# FPGA_PPU.net
KiCad netlist of a schematic drawn in EAGLE
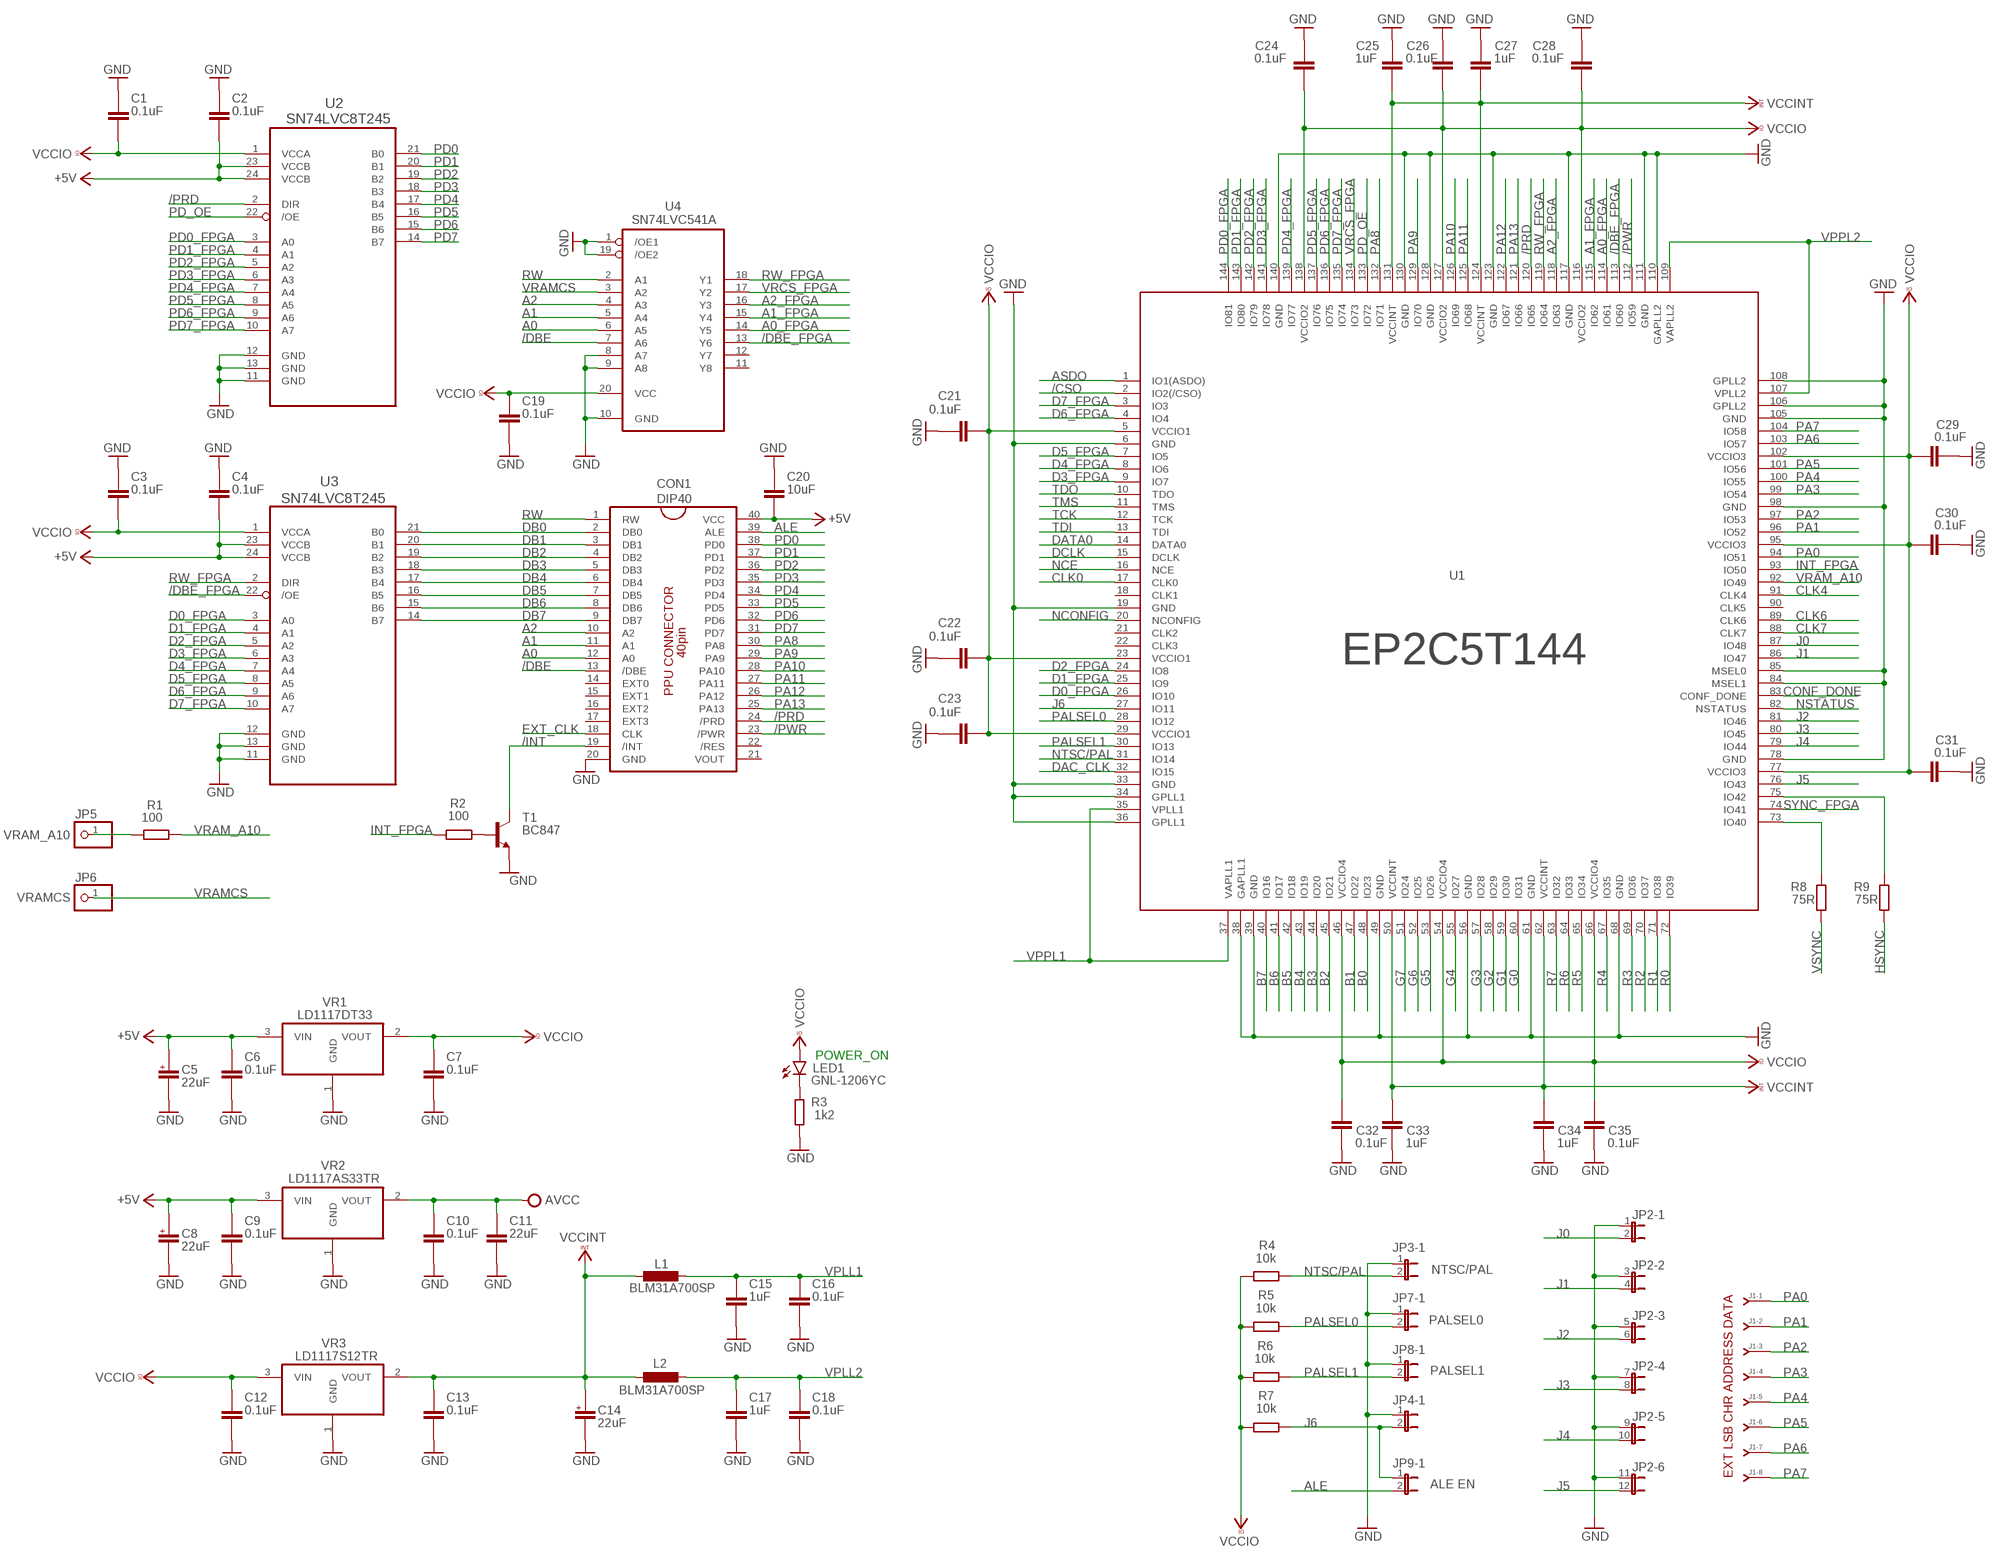
[diagram p0: schematic, sheet 1, part 1 of 2]
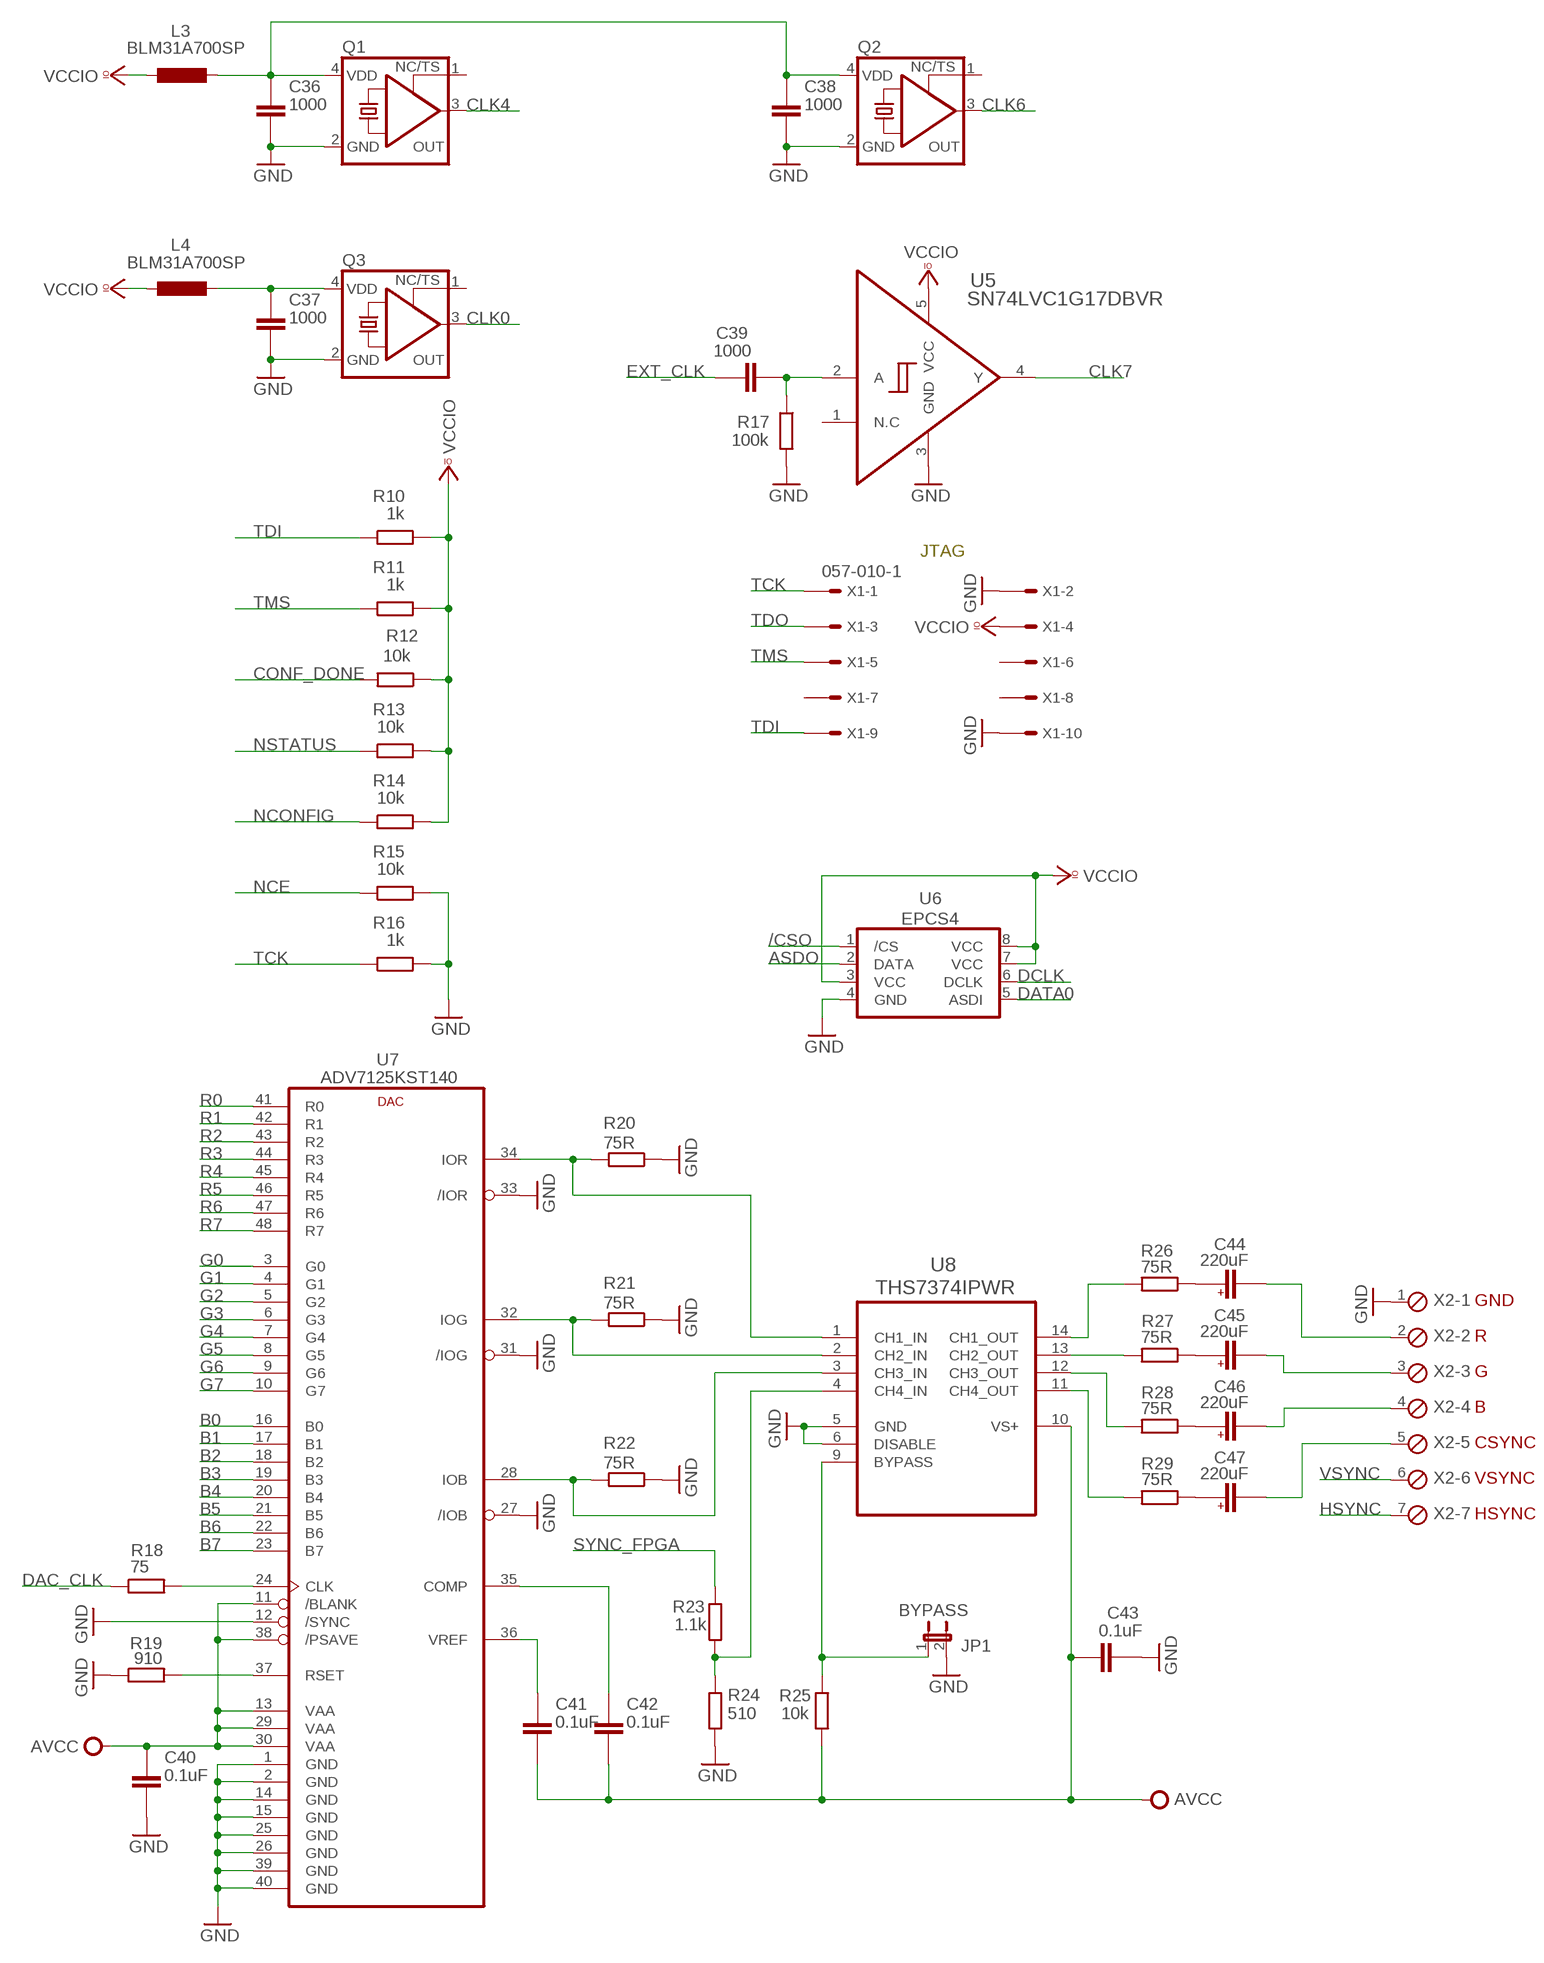
[diagram p1: schematic, sheet 1, part 2 of 2]

(export (version "E")
  (design (tool "Eeschema 10.0.6"))
  (components
    (comp (ref "C1")
      (value "0.1uF")
      (footprint "eagle-import:C0805")
      (libsource (lib "eagle-import") (part "C-EUC0805"))
    )
    (comp (ref "C2")
      (value "0.1uF")
      (footprint "eagle-import:C0805")
      (libsource (lib "eagle-import") (part "C-EUC0805"))
    )
    (comp (ref "C3")
      (value "0.1uF")
      (footprint "eagle-import:C0805")
      (libsource (lib "eagle-import") (part "C-EUC0805"))
    )
    (comp (ref "C4")
      (value "0.1uF")
      (footprint "eagle-import:C0805")
      (libsource (lib "eagle-import") (part "C-EUC0805"))
    )
    (comp (ref "C5")
      (value "22uF")
      (footprint "eagle-import:153CLV-0505")
      (libsource (lib "eagle-import") (part "CPOL-EU153CLV-0505"))
    )
    (comp (ref "C6")
      (value "0.1uF")
      (footprint "eagle-import:C0805")
      (libsource (lib "eagle-import") (part "C-EUC0805"))
    )
    (comp (ref "C7")
      (value "0.1uF")
      (footprint "eagle-import:C0805")
      (libsource (lib "eagle-import") (part "C-EUC0805"))
    )
    (comp (ref "C8")
      (value "22uF")
      (footprint "eagle-import:153CLV-0505")
      (libsource (lib "eagle-import") (part "CPOL-EU153CLV-0505"))
    )
    (comp (ref "C9")
      (value "0.1uF")
      (footprint "eagle-import:C0805")
      (libsource (lib "eagle-import") (part "C-EUC0805"))
    )
    (comp (ref "C10")
      (value "0.1uF")
      (footprint "eagle-import:C0805")
      (libsource (lib "eagle-import") (part "C-EUC0805"))
    )
    (comp (ref "C11")
      (value "22uF")
      (footprint "eagle-import:C0805")
      (libsource (lib "eagle-import") (part "C-EUC0805"))
    )
    (comp (ref "C12")
      (value "0.1uF")
      (footprint "eagle-import:C0805")
      (libsource (lib "eagle-import") (part "C-EUC0805"))
    )
    (comp (ref "C13")
      (value "0.1uF")
      (footprint "eagle-import:C0805")
      (libsource (lib "eagle-import") (part "C-EUC0805"))
    )
    (comp (ref "C14")
      (value "22uF")
      (footprint "eagle-import:153CLV-0505")
      (libsource (lib "eagle-import") (part "CPOL-EU153CLV-0505"))
    )
    (comp (ref "C15")
      (value "1uF")
      (footprint "eagle-import:C0805")
      (libsource (lib "eagle-import") (part "C-EUC0805"))
    )
    (comp (ref "C16")
      (value "0.1uF")
      (footprint "eagle-import:C0805")
      (libsource (lib "eagle-import") (part "C-EUC0805"))
    )
    (comp (ref "C17")
      (value "1uF")
      (footprint "eagle-import:C0805")
      (libsource (lib "eagle-import") (part "C-EUC0805"))
    )
    (comp (ref "C18")
      (value "0.1uF")
      (footprint "eagle-import:C0805")
      (libsource (lib "eagle-import") (part "C-EUC0805"))
    )
    (comp (ref "C19")
      (value "0.1uF")
      (footprint "eagle-import:C0805")
      (libsource (lib "eagle-import") (part "C-EUC0805"))
    )
    (comp (ref "C20")
      (value "10uF")
      (footprint "eagle-import:C0805")
      (libsource (lib "eagle-import") (part "C-EUC0805"))
    )
    (comp (ref "C21")
      (value "0.1uF")
      (footprint "eagle-import:C0805")
      (libsource (lib "eagle-import") (part "C-EUC0805"))
    )
    (comp (ref "C22")
      (value "0.1uF")
      (footprint "eagle-import:C0805")
      (libsource (lib "eagle-import") (part "C-EUC0805"))
    )
    (comp (ref "C23")
      (value "0.1uF")
      (footprint "eagle-import:C0805")
      (libsource (lib "eagle-import") (part "C-EUC0805"))
    )
    (comp (ref "C24")
      (value "0.1uF")
      (footprint "eagle-import:C0805")
      (libsource (lib "eagle-import") (part "C-EUC0805"))
    )
    (comp (ref "C25")
      (value "1uF")
      (footprint "eagle-import:C0805")
      (libsource (lib "eagle-import") (part "C-EUC0805"))
    )
    (comp (ref "C26")
      (value "0.1uF")
      (footprint "eagle-import:C0805")
      (libsource (lib "eagle-import") (part "C-EUC0805"))
    )
    (comp (ref "C27")
      (value "1uF")
      (footprint "eagle-import:C0805")
      (libsource (lib "eagle-import") (part "C-EUC0805"))
    )
    (comp (ref "C28")
      (value "0.1uF")
      (footprint "eagle-import:C0805")
      (libsource (lib "eagle-import") (part "C-EUC0805"))
    )
    (comp (ref "C29")
      (value "0.1uF")
      (footprint "eagle-import:C0805")
      (libsource (lib "eagle-import") (part "C-EUC0805"))
    )
    (comp (ref "C30")
      (value "0.1uF")
      (footprint "eagle-import:C0805")
      (libsource (lib "eagle-import") (part "C-EUC0805"))
    )
    (comp (ref "C31")
      (value "0.1uF")
      (footprint "eagle-import:C0805")
      (libsource (lib "eagle-import") (part "C-EUC0805"))
    )
    (comp (ref "C32")
      (value "0.1uF")
      (footprint "eagle-import:C0805")
      (libsource (lib "eagle-import") (part "C-EUC0805"))
    )
    (comp (ref "C33")
      (value "1uF")
      (footprint "eagle-import:C0805")
      (libsource (lib "eagle-import") (part "C-EUC0805"))
    )
    (comp (ref "C34")
      (value "1uF")
      (footprint "eagle-import:C0805")
      (libsource (lib "eagle-import") (part "C-EUC0805"))
    )
    (comp (ref "C35")
      (value "0.1uF")
      (footprint "eagle-import:C0805")
      (libsource (lib "eagle-import") (part "C-EUC0805"))
    )
    (comp (ref "C36")
      (value "1000")
      (footprint "eagle-import:C0805")
      (libsource (lib "eagle-import") (part "C-EUC0805"))
    )
    (comp (ref "C37")
      (value "1000")
      (footprint "eagle-import:C0805")
      (libsource (lib "eagle-import") (part "C-EUC0805"))
    )
    (comp (ref "C38")
      (value "1000")
      (footprint "eagle-import:C0805")
      (libsource (lib "eagle-import") (part "C-EUC0805"))
    )
    (comp (ref "C39")
      (value "1000")
      (footprint "eagle-import:C0805")
      (libsource (lib "eagle-import") (part "C-EUC0805"))
    )
    (comp (ref "C40")
      (value "0.1uF")
      (footprint "eagle-import:C0805")
      (libsource (lib "eagle-import") (part "C-EUC0805"))
    )
    (comp (ref "C41")
      (value "0.1uF")
      (footprint "eagle-import:C0805")
      (libsource (lib "eagle-import") (part "C-EUC0805"))
    )
    (comp (ref "C42")
      (value "0.1uF")
      (footprint "eagle-import:C0805")
      (libsource (lib "eagle-import") (part "C-EUC0805"))
    )
    (comp (ref "C43")
      (value "0.1uF")
      (footprint "eagle-import:C0805")
      (libsource (lib "eagle-import") (part "C-EUC0805"))
    )
    (comp (ref "C44")
      (value "220uF")
      (footprint "eagle-import:153CLV-0505")
      (libsource (lib "eagle-import") (part "CPOL-EU153CLV-0505"))
    )
    (comp (ref "C45")
      (value "220uF")
      (footprint "eagle-import:153CLV-0505")
      (libsource (lib "eagle-import") (part "CPOL-EU153CLV-0505"))
    )
    (comp (ref "C46")
      (value "220uF")
      (footprint "eagle-import:153CLV-0505")
      (libsource (lib "eagle-import") (part "CPOL-EU153CLV-0505"))
    )
    (comp (ref "C47")
      (value "220uF")
      (footprint "eagle-import:153CLV-0505")
      (libsource (lib "eagle-import") (part "CPOL-EU153CLV-0505"))
    )
    (comp (ref "CON1")
      (value "DIP40")
      (footprint "eagle-import:DIP-40")
      (libsource (lib "eagle-import") (part "DIP40"))
    )
    (comp (ref "J1")
      (value "J-08-SIP-100")
      (footprint "eagle-import:SIP-100-08")
      (libsource (lib "eagle-import") (part "J-08-SIP-100"))
    )
    (comp (ref "JP1")
      (value "BYPASS")
      (footprint "eagle-import:JP1")
      (libsource (lib "eagle-import") (part "JP1E"))
    )
    (comp (ref "JP2")
      (value "JP6QE")
      (footprint "eagle-import:JP6Q")
      (libsource (lib "eagle-import") (part "JP6QE"))
    )
    (comp (ref "JP3")
      (value "NTSC/PAL")
      (footprint "eagle-import:JP4Q")
      (libsource (lib "eagle-import") (part "JP4QE"))
    )
    (comp (ref "JP4")
      (value "JP4QE")
      (footprint "eagle-import:JP4Q")
      (libsource (lib "eagle-import") (part "JP4QE"))
    )
    (comp (ref "JP5")
      (value "VRAM_A10")
      (footprint "eagle-import:1X01")
      (libsource (lib "eagle-import") (part "PINHD-1X1"))
    )
    (comp (ref "JP6")
      (value "VRAMCS")
      (footprint "eagle-import:1X01")
      (libsource (lib "eagle-import") (part "PINHD-1X1"))
    )
    (comp (ref "JP7")
      (value "PALSEL0")
      (footprint "eagle-import:JP4Q")
      (libsource (lib "eagle-import") (part "JP4QE"))
    )
    (comp (ref "JP8")
      (value "PALSEL1")
      (footprint "eagle-import:JP4Q")
      (libsource (lib "eagle-import") (part "JP4QE"))
    )
    (comp (ref "JP9")
      (value "ALE EN")
      (footprint "eagle-import:JP4Q")
      (libsource (lib "eagle-import") (part "JP4QE"))
    )
    (comp (ref "L1")
      (value "BLM31A700SP")
      (footprint "eagle-import:L2012C")
      (libsource (lib "eagle-import") (part "L-EUL2012C"))
    )
    (comp (ref "L2")
      (value "BLM31A700SP")
      (footprint "eagle-import:L2012C")
      (libsource (lib "eagle-import") (part "L-EUL2012C"))
    )
    (comp (ref "L3")
      (value "BLM31A700SP")
      (footprint "eagle-import:L2012C")
      (libsource (lib "eagle-import") (part "L-EUL2012C"))
    )
    (comp (ref "L4")
      (value "BLM31A700SP")
      (footprint "eagle-import:L2012C")
      (libsource (lib "eagle-import") (part "L-EUL2012C"))
    )
    (comp (ref "LED1")
      (value "GNL-1206YC")
      (footprint "eagle-import:SMARTLED-TTW")
      (libsource (lib "eagle-import") (part "LED"))
    )
    (comp (ref "Q1")
      (value "KXO-PXO/XO-V97")
      (footprint "eagle-import:7.0X5.08_KXO-(V)97")
      (libsource (lib "eagle-import") (part "KXO-PXO/XO-V97"))
    )
    (comp (ref "Q2")
      (value "KXO-PXO/XO-V95")
      (footprint "eagle-import:2.5X2.0_KXO-V95")
      (libsource (lib "eagle-import") (part "KXO-PXO/XO-V95"))
    )
    (comp (ref "Q3")
      (value "KXO-PXO/XO-V95")
      (footprint "eagle-import:2.5X2.0_KXO-V95")
      (libsource (lib "eagle-import") (part "KXO-PXO/XO-V95"))
    )
    (comp (ref "R1")
      (value "100")
      (footprint "eagle-import:R0805")
      (libsource (lib "eagle-import") (part "R-EU_R0805"))
    )
    (comp (ref "R2")
      (value "100")
      (footprint "eagle-import:R0805")
      (libsource (lib "eagle-import") (part "R-EU_R0805"))
    )
    (comp (ref "R3")
      (value "1k2")
      (footprint "eagle-import:R0805")
      (libsource (lib "eagle-import") (part "R-EU_R0805"))
    )
    (comp (ref "R4")
      (value "10k")
      (footprint "eagle-import:R0805")
      (libsource (lib "eagle-import") (part "R-EU_R0805"))
    )
    (comp (ref "R5")
      (value "10k")
      (footprint "eagle-import:R0805")
      (libsource (lib "eagle-import") (part "R-EU_R0805"))
    )
    (comp (ref "R6")
      (value "10k")
      (footprint "eagle-import:R0805")
      (libsource (lib "eagle-import") (part "R-EU_R0805"))
    )
    (comp (ref "R7")
      (value "10k")
      (footprint "eagle-import:R0805")
      (libsource (lib "eagle-import") (part "R-EU_R0805"))
    )
    (comp (ref "R8")
      (value "75R")
      (footprint "eagle-import:R0805")
      (libsource (lib "eagle-import") (part "R-EU_R0805"))
    )
    (comp (ref "R9")
      (value "75R")
      (footprint "eagle-import:R0805")
      (libsource (lib "eagle-import") (part "R-EU_R0805"))
    )
    (comp (ref "R10")
      (value "1k")
      (footprint "eagle-import:R0805")
      (libsource (lib "eagle-import") (part "R-EU_R0805"))
    )
    (comp (ref "R11")
      (value "1k")
      (footprint "eagle-import:R0805")
      (libsource (lib "eagle-import") (part "R-EU_R0805"))
    )
    (comp (ref "R12")
      (value "10k")
      (footprint "eagle-import:R0805")
      (libsource (lib "eagle-import") (part "R-EU_R0805"))
    )
    (comp (ref "R13")
      (value "10k")
      (footprint "eagle-import:R0805")
      (libsource (lib "eagle-import") (part "R-EU_R0805"))
    )
    (comp (ref "R14")
      (value "10k")
      (footprint "eagle-import:R0805")
      (libsource (lib "eagle-import") (part "R-EU_R0805"))
    )
    (comp (ref "R15")
      (value "10k")
      (footprint "eagle-import:R0805")
      (libsource (lib "eagle-import") (part "R-EU_R0805"))
    )
    (comp (ref "R16")
      (value "1k")
      (footprint "eagle-import:R0805")
      (libsource (lib "eagle-import") (part "R-EU_R0805"))
    )
    (comp (ref "R17")
      (value "100k")
      (footprint "eagle-import:R0805")
      (libsource (lib "eagle-import") (part "R-EU_R0805"))
    )
    (comp (ref "R18")
      (value "75")
      (footprint "eagle-import:R0805")
      (libsource (lib "eagle-import") (part "R-EU_R0805"))
    )
    (comp (ref "R19")
      (value "910")
      (footprint "eagle-import:R0805")
      (libsource (lib "eagle-import") (part "R-EU_R0805"))
    )
    (comp (ref "R20")
      (value "75R")
      (footprint "eagle-import:R0805")
      (libsource (lib "eagle-import") (part "R-EU_R0805"))
    )
    (comp (ref "R21")
      (value "75R")
      (footprint "eagle-import:R0805")
      (libsource (lib "eagle-import") (part "R-EU_R0805"))
    )
    (comp (ref "R22")
      (value "75R")
      (footprint "eagle-import:R0805")
      (libsource (lib "eagle-import") (part "R-EU_R0805"))
    )
    (comp (ref "R23")
      (value "1.1k")
      (footprint "eagle-import:R0805")
      (libsource (lib "eagle-import") (part "R-EU_R0805"))
    )
    (comp (ref "R24")
      (value "510")
      (footprint "eagle-import:R0805")
      (libsource (lib "eagle-import") (part "R-EU_R0805"))
    )
    (comp (ref "R25")
      (value "10k")
      (footprint "eagle-import:R0805")
      (libsource (lib "eagle-import") (part "R-EU_R0805"))
    )
    (comp (ref "R26")
      (value "75R")
      (footprint "eagle-import:R0805")
      (libsource (lib "eagle-import") (part "R-EU_R0805"))
    )
    (comp (ref "R27")
      (value "75R")
      (footprint "eagle-import:R0805")
      (libsource (lib "eagle-import") (part "R-EU_R0805"))
    )
    (comp (ref "R28")
      (value "75R")
      (footprint "eagle-import:R0805")
      (libsource (lib "eagle-import") (part "R-EU_R0805"))
    )
    (comp (ref "R29")
      (value "75R")
      (footprint "eagle-import:R0805")
      (libsource (lib "eagle-import") (part "R-EU_R0805"))
    )
    (comp (ref "T1")
      (value "BC847")
      (footprint "eagle-import:SOT23")
      (libsource (lib "eagle-import") (part "BC847"))
    )
    (comp (ref "U1")
      (value "EP2C5T144")
      (footprint "eagle-import:TQFP144")
      (fields (field (name "MPN") "EP2C5T144C8N"))
      (libsource (lib "eagle-import") (part "EP2C5T144"))
    )
    (comp (ref "U2")
      (value "SN74LVC8T245")
      (footprint "eagle-import:SOP65P640X110-24N")
      (libsource (lib "eagle-import") (part "SN74LVC8T245"))
    )
    (comp (ref "U3")
      (value "SN74LVC8T245")
      (footprint "eagle-import:SOP65P640X110-24N")
      (libsource (lib "eagle-import") (part "SN74LVC8T245"))
    )
    (comp (ref "U4")
      (value "SN74LVC541A")
      (footprint "eagle-import:TSOP20")
      (libsource (lib "eagle-import") (part "SN74LVC541A"))
    )
    (comp (ref "U5")
      (value "SN74LVC1G17DBVR")
      (footprint "eagle-import:SOT95P280X145-5N")
      (libsource (lib "eagle-import") (part "SN74LVC1G17DBVR"))
    )
    (comp (ref "U6")
      (value "EPCS4")
      (footprint "eagle-import:SO08")
      (libsource (lib "eagle-import") (part "EPCS4"))
    )
    (comp (ref "U7")
      (value "ADV7125KST140")
      (footprint "eagle-import:QFP50P900X900X160-48N")
      (fields (field (name "MANUFACTURER") "Analog Devices"))
      (libsource (lib "eagle-import") (part "ADV7125KST140"))
    )
    (comp (ref "U8")
      (value "THS7374IPWR")
      (footprint "eagle-import:SOP65P640X120-14N")
      (libsource (lib "eagle-import") (part "THS7374IPWR"))
    )
    (comp (ref "VR1")
      (value "LD1117DT33")
      (footprint "eagle-import:DPAK456P1010X240-3N")
      (fields (field (name "MANUFACTURER") "STMicroelectronics"))
      (libsource (lib "eagle-import") (part "LD1117DT33"))
    )
    (comp (ref "VR2")
      (value "LD1117AS33TR")
      (footprint "eagle-import:SOT230P700X180-4N")
      (libsource (lib "eagle-import") (part "LD1117AS33TR"))
    )
    (comp (ref "VR3")
      (value "LD1117S12TR")
      (footprint "eagle-import:SOT-223-3")
      (libsource (lib "eagle-import") (part "LD1117S12TR"))
    )
    (comp (ref "X1")
      (value "057-010-1")
      (footprint "eagle-import:057-010-1")
      (libsource (lib "eagle-import") (part "057-010-1"))
    )
    (comp (ref "X2")
      (value "MPT7")
      (footprint "eagle-import:7POL254")
      (libsource (lib "eagle-import") (part "MPT7"))
    )
  )
  (nets
    (net (code "1") (name "+5V") (class "Default")
      (node (ref "C2") (pin "2") (pinfunction "2_2") (pintype "passive"))
      (node (ref "C20") (pin "2") (pinfunction "2_2") (pintype "passive"))
      (node (ref "C4") (pin "2") (pinfunction "2_2") (pintype "passive"))
      (node (ref "C5") (pin "+") (pinfunction "+_+") (pintype "passive"))
      (node (ref "C6") (pin "1") (pinfunction "1_1") (pintype "passive"))
      (node (ref "C8") (pin "+") (pinfunction "+_+") (pintype "passive"))
      (node (ref "C9") (pin "1") (pinfunction "1_1") (pintype "passive"))
      (node (ref "CON1") (pin "40") (pinfunction "VCC_40") (pintype "power_in"))
      (node (ref "U2") (pin "23") (pinfunction "VCCB_23") (pintype "power_in"))
      (node (ref "U2") (pin "24") (pinfunction "VCCB_24") (pintype "power_in"))
      (node (ref "U3") (pin "23") (pinfunction "VCCB_23") (pintype "power_in"))
      (node (ref "U3") (pin "24") (pinfunction "VCCB_24") (pintype "power_in"))
      (node (ref "VR1") (pin "3") (pinfunction "VIN_3") (pintype "power_in"))
      (node (ref "VR2") (pin "3") (pinfunction "VIN_3") (pintype "power_in"))
    )
    (net (code "2") (name "/A0") (class "Default")
      (node (ref "CON1") (pin "12") (pinfunction "A0_12") (pintype "output"))
      (node (ref "U4") (pin "6") (pinfunction "A5_6") (pintype "input"))
    )
    (net (code "3") (name "/A0_FPGA") (class "Default")
      (node (ref "U1") (pin "114") (pinfunction "IO61_114") (pintype "bidirectional"))
      (node (ref "U4") (pin "14") (pinfunction "Y5_14") (pintype "output"))
    )
    (net (code "4") (name "/A1") (class "Default")
      (node (ref "CON1") (pin "11") (pinfunction "A1_11") (pintype "output"))
      (node (ref "U4") (pin "5") (pinfunction "A4_5") (pintype "input"))
    )
    (net (code "5") (name "/A1_FPGA") (class "Default")
      (node (ref "U1") (pin "115") (pinfunction "IO62_115") (pintype "bidirectional"))
      (node (ref "U4") (pin "15") (pinfunction "Y4_15") (pintype "output"))
    )
    (net (code "6") (name "/A2") (class "Default")
      (node (ref "CON1") (pin "10") (pinfunction "A2_10") (pintype "output"))
      (node (ref "U4") (pin "4") (pinfunction "A3_4") (pintype "input"))
    )
    (net (code "7") (name "/A2_FPGA") (class "Default")
      (node (ref "U1") (pin "118") (pinfunction "IO63_118") (pintype "bidirectional"))
      (node (ref "U4") (pin "16") (pinfunction "Y3_16") (pintype "output"))
    )
    (net (code "8") (name "/ALE") (class "Default")
      (node (ref "CON1") (pin "39") (pinfunction "ALE_39") (pintype "input"))
      (node (ref "JP9") (pin "2") (pinfunction "2_2") (pintype "passive"))
    )
    (net (code "9") (name "/ASDO") (class "Default")
      (node (ref "U1") (pin "1") (pinfunction "IO1(ASDO)_1") (pintype "bidirectional"))
      (node (ref "U6") (pin "2") (pinfunction "DATA_2") (pintype "output"))
    )
    (net (code "10") (name "/B0") (class "Default")
      (node (ref "U1") (pin "48") (pinfunction "IO23_48") (pintype "bidirectional"))
      (node (ref "U7") (pin "16") (pinfunction "B0_16") (pintype "input"))
    )
    (net (code "11") (name "/B1") (class "Default")
      (node (ref "U1") (pin "47") (pinfunction "IO22_47") (pintype "bidirectional"))
      (node (ref "U7") (pin "17") (pinfunction "B1_17") (pintype "input"))
    )
    (net (code "12") (name "/B2") (class "Default")
      (node (ref "U1") (pin "45") (pinfunction "IO21_45") (pintype "bidirectional"))
      (node (ref "U7") (pin "18") (pinfunction "B2_18") (pintype "input"))
    )
    (net (code "13") (name "/B3") (class "Default")
      (node (ref "U1") (pin "44") (pinfunction "IO20_44") (pintype "bidirectional"))
      (node (ref "U7") (pin "19") (pinfunction "B3_19") (pintype "input"))
    )
    (net (code "14") (name "/B4") (class "Default")
      (node (ref "U1") (pin "43") (pinfunction "IO19_43") (pintype "bidirectional"))
      (node (ref "U7") (pin "20") (pinfunction "B4_20") (pintype "input"))
    )
    (net (code "15") (name "/B5") (class "Default")
      (node (ref "U1") (pin "42") (pinfunction "IO18_42") (pintype "bidirectional"))
      (node (ref "U7") (pin "21") (pinfunction "B5_21") (pintype "input"))
    )
    (net (code "16") (name "/B6") (class "Default")
      (node (ref "U1") (pin "41") (pinfunction "IO17_41") (pintype "bidirectional"))
      (node (ref "U7") (pin "22") (pinfunction "B6_22") (pintype "input"))
    )
    (net (code "17") (name "/B7") (class "Default")
      (node (ref "U1") (pin "40") (pinfunction "IO16_40") (pintype "bidirectional"))
      (node (ref "U7") (pin "23") (pinfunction "B7_23") (pintype "input"))
    )
    (net (code "18") (name "/CLK0") (class "Default")
      (node (ref "Q3") (pin "3") (pinfunction "OUT_3") (pintype "output"))
      (node (ref "U1") (pin "17") (pinfunction "CLK0_17") (pintype "input"))
    )
    (net (code "19") (name "/CLK4") (class "Default")
      (node (ref "Q1") (pin "3") (pinfunction "OUT_3") (pintype "output"))
      (node (ref "U1") (pin "91") (pinfunction "CLK4_91") (pintype "input"))
    )
    (net (code "20") (name "/CLK6") (class "Default")
      (node (ref "Q2") (pin "3") (pinfunction "OUT_3") (pintype "output"))
      (node (ref "U1") (pin "89") (pinfunction "CLK6_89") (pintype "input"))
    )
    (net (code "21") (name "/CLK7") (class "Default")
      (node (ref "U1") (pin "88") (pinfunction "CLK7_88") (pintype "input"))
      (node (ref "U5") (pin "4") (pinfunction "Y_4") (pintype "output"))
    )
    (net (code "22") (name "/CONF_DONE") (class "Default")
      (node (ref "R12") (pin "2") (pinfunction "2_2") (pintype "passive"))
      (node (ref "U1") (pin "83") (pinfunction "CONF_DONE_83") (pintype "bidirectional"))
    )
    (net (code "23") (name "/D0_FPGA") (class "Default")
      (node (ref "U1") (pin "26") (pinfunction "IO10_26") (pintype "bidirectional"))
      (node (ref "U3") (pin "3") (pinfunction "A0_3") (pintype "bidirectional"))
    )
    (net (code "24") (name "/D1_FPGA") (class "Default")
      (node (ref "U1") (pin "25") (pinfunction "IO9_25") (pintype "bidirectional"))
      (node (ref "U3") (pin "4") (pinfunction "A1_4") (pintype "bidirectional"))
    )
    (net (code "25") (name "/D2_FPGA") (class "Default")
      (node (ref "U1") (pin "24") (pinfunction "IO8_24") (pintype "bidirectional"))
      (node (ref "U3") (pin "5") (pinfunction "A2_5") (pintype "bidirectional"))
    )
    (net (code "26") (name "/D3_FPGA") (class "Default")
      (node (ref "U1") (pin "9") (pinfunction "IO7_9") (pintype "bidirectional"))
      (node (ref "U3") (pin "6") (pinfunction "A3_6") (pintype "bidirectional"))
    )
    (net (code "27") (name "/D4_FPGA") (class "Default")
      (node (ref "U1") (pin "8") (pinfunction "IO6_8") (pintype "bidirectional"))
      (node (ref "U3") (pin "7") (pinfunction "A4_7") (pintype "bidirectional"))
    )
    (net (code "28") (name "/D5_FPGA") (class "Default")
      (node (ref "U1") (pin "7") (pinfunction "IO5_7") (pintype "bidirectional"))
      (node (ref "U3") (pin "8") (pinfunction "A5_8") (pintype "bidirectional"))
    )
    (net (code "29") (name "/D6_FPGA") (class "Default")
      (node (ref "U1") (pin "4") (pinfunction "IO4_4") (pintype "bidirectional"))
      (node (ref "U3") (pin "9") (pinfunction "A6_9") (pintype "bidirectional"))
    )
    (net (code "30") (name "/D7_FPGA") (class "Default")
      (node (ref "U1") (pin "3") (pinfunction "IO3_3") (pintype "bidirectional"))
      (node (ref "U3") (pin "10") (pinfunction "A7_10") (pintype "bidirectional"))
    )
    (net (code "31") (name "/DAC_CLK") (class "Default")
      (node (ref "R18") (pin "1") (pinfunction "1_1") (pintype "passive"))
      (node (ref "U1") (pin "32") (pinfunction "IO15_32") (pintype "bidirectional"))
    )
    (net (code "32") (name "/DATA0") (class "Default")
      (node (ref "U1") (pin "14") (pinfunction "DATA0_14") (pintype "bidirectional"))
      (node (ref "U6") (pin "5") (pinfunction "ASDI_5") (pintype "input"))
    )
    (net (code "33") (name "/DB0") (class "Default")
      (node (ref "CON1") (pin "2") (pinfunction "DB0_2") (pintype "bidirectional"))
      (node (ref "U3") (pin "21") (pinfunction "B0_21") (pintype "bidirectional"))
    )
    (net (code "34") (name "/DB1") (class "Default")
      (node (ref "CON1") (pin "3") (pinfunction "DB1_3") (pintype "bidirectional"))
      (node (ref "U3") (pin "20") (pinfunction "B1_20") (pintype "bidirectional"))
    )
    (net (code "35") (name "/DB2") (class "Default")
      (node (ref "CON1") (pin "4") (pinfunction "DB2_4") (pintype "bidirectional"))
      (node (ref "U3") (pin "19") (pinfunction "B2_19") (pintype "bidirectional"))
    )
    (net (code "36") (name "/DB3") (class "Default")
      (node (ref "CON1") (pin "5") (pinfunction "DB3_5") (pintype "bidirectional"))
      (node (ref "U3") (pin "18") (pinfunction "B3_18") (pintype "bidirectional"))
    )
    (net (code "37") (name "/DB4") (class "Default")
      (node (ref "CON1") (pin "6") (pinfunction "DB4_6") (pintype "bidirectional"))
      (node (ref "U3") (pin "17") (pinfunction "B4_17") (pintype "bidirectional"))
    )
    (net (code "38") (name "/DB5") (class "Default")
      (node (ref "CON1") (pin "7") (pinfunction "DB5_7") (pintype "bidirectional"))
      (node (ref "U3") (pin "16") (pinfunction "B5_16") (pintype "bidirectional"))
    )
    (net (code "39") (name "/DB6") (class "Default")
      (node (ref "CON1") (pin "8") (pinfunction "DB6_8") (pintype "bidirectional"))
      (node (ref "U3") (pin "15") (pinfunction "B6_15") (pintype "bidirectional"))
    )
    (net (code "40") (name "/DB7") (class "Default")
      (node (ref "CON1") (pin "9") (pinfunction "DB7_9") (pintype "bidirectional"))
      (node (ref "U3") (pin "14") (pinfunction "B7_14") (pintype "bidirectional"))
    )
    (net (code "41") (name "/DCLK") (class "Default")
      (node (ref "U1") (pin "15") (pinfunction "DCLK_15") (pintype "bidirectional"))
      (node (ref "U6") (pin "6") (pinfunction "DCLK_6") (pintype "input"))
    )
    (net (code "42") (name "/EXT_CLK") (class "Default")
      (node (ref "C39") (pin "1") (pinfunction "1_1") (pintype "passive"))
      (node (ref "CON1") (pin "18") (pinfunction "CLK_18") (pintype "output"))
    )
    (net (code "43") (name "/G0") (class "Default")
      (node (ref "U1") (pin "60") (pinfunction "IO31_60") (pintype "bidirectional"))
      (node (ref "U7") (pin "3") (pinfunction "G0_3") (pintype "input"))
    )
    (net (code "44") (name "/G1") (class "Default")
      (node (ref "U1") (pin "59") (pinfunction "IO30_59") (pintype "bidirectional"))
      (node (ref "U7") (pin "4") (pinfunction "G1_4") (pintype "input"))
    )
    (net (code "45") (name "/G2") (class "Default")
      (node (ref "U1") (pin "58") (pinfunction "IO29_58") (pintype "bidirectional"))
      (node (ref "U7") (pin "5") (pinfunction "G2_5") (pintype "input"))
    )
    (net (code "46") (name "/G3") (class "Default")
      (node (ref "U1") (pin "57") (pinfunction "IO28_57") (pintype "bidirectional"))
      (node (ref "U7") (pin "6") (pinfunction "G3_6") (pintype "input"))
    )
    (net (code "47") (name "/G4") (class "Default")
      (node (ref "U1") (pin "55") (pinfunction "IO27_55") (pintype "bidirectional"))
      (node (ref "U7") (pin "7") (pinfunction "G4_7") (pintype "input"))
    )
    (net (code "48") (name "/G5") (class "Default")
      (node (ref "U1") (pin "53") (pinfunction "IO26_53") (pintype "bidirectional"))
      (node (ref "U7") (pin "8") (pinfunction "G5_8") (pintype "input"))
    )
    (net (code "49") (name "/G6") (class "Default")
      (node (ref "U1") (pin "52") (pinfunction "IO25_52") (pintype "bidirectional"))
      (node (ref "U7") (pin "9") (pinfunction "G6_9") (pintype "input"))
    )
    (net (code "50") (name "/G7") (class "Default")
      (node (ref "U1") (pin "51") (pinfunction "IO24_51") (pintype "bidirectional"))
      (node (ref "U7") (pin "10") (pinfunction "G7_10") (pintype "input"))
    )
    (net (code "51") (name "/HSYNC") (class "Default")
      (node (ref "R9") (pin "2") (pinfunction "2_2") (pintype "passive"))
      (node (ref "X2") (pin "7") (pinfunction "1_7") (pintype "passive"))
    )
    (net (code "52") (name "/INT_FPGA") (class "Default")
      (node (ref "R2") (pin "2") (pinfunction "2_2") (pintype "passive"))
      (node (ref "U1") (pin "93") (pinfunction "IO50_93") (pintype "bidirectional"))
    )
    (net (code "53") (name "/J0") (class "Default")
      (node (ref "JP2") (pin "2") (pinfunction "2_2") (pintype "passive"))
      (node (ref "U1") (pin "87") (pinfunction "IO48_87") (pintype "bidirectional"))
    )
    (net (code "54") (name "/J1") (class "Default")
      (node (ref "JP2") (pin "4") (pinfunction "2_4") (pintype "passive"))
      (node (ref "U1") (pin "86") (pinfunction "IO47_86") (pintype "bidirectional"))
    )
    (net (code "55") (name "/J2") (class "Default")
      (node (ref "JP2") (pin "6") (pinfunction "2_6") (pintype "passive"))
      (node (ref "U1") (pin "81") (pinfunction "IO46_81") (pintype "bidirectional"))
    )
    (net (code "56") (name "/J3") (class "Default")
      (node (ref "JP2") (pin "8") (pinfunction "2_8") (pintype "passive"))
      (node (ref "U1") (pin "80") (pinfunction "IO45_80") (pintype "bidirectional"))
    )
    (net (code "57") (name "/J4") (class "Default")
      (node (ref "JP2") (pin "10") (pinfunction "2_10") (pintype "passive"))
      (node (ref "U1") (pin "79") (pinfunction "IO44_79") (pintype "bidirectional"))
    )
    (net (code "58") (name "/J5") (class "Default")
      (node (ref "JP2") (pin "12") (pinfunction "2_12") (pintype "passive"))
      (node (ref "U1") (pin "76") (pinfunction "IO43_76") (pintype "bidirectional"))
    )
    (net (code "59") (name "/J6") (class "Default")
      (node (ref "JP4") (pin "2") (pinfunction "2_2") (pintype "passive"))
      (node (ref "JP9") (pin "1") (pinfunction "1_1") (pintype "passive"))
      (node (ref "R7") (pin "2") (pinfunction "2_2") (pintype "passive"))
      (node (ref "U1") (pin "27") (pinfunction "IO11_27") (pintype "bidirectional"))
    )
    (net (code "60") (name "/NCE") (class "Default")
      (node (ref "R15") (pin "1") (pinfunction "1_1") (pintype "passive"))
      (node (ref "U1") (pin "16") (pinfunction "NCE_16") (pintype "input"))
    )
    (net (code "61") (name "/NCONFIG") (class "Default")
      (node (ref "R14") (pin "1") (pinfunction "1_1") (pintype "passive"))
      (node (ref "U1") (pin "20") (pinfunction "NCONFIG_20") (pintype "input"))
    )
    (net (code "62") (name "/NSTATUS") (class "Default")
      (node (ref "R13") (pin "1") (pinfunction "1_1") (pintype "passive"))
      (node (ref "U1") (pin "82") (pinfunction "NSTATUS_82") (pintype "bidirectional"))
    )
    (net (code "63") (name "/NTSC{slash}PAL") (class "Default")
      (node (ref "JP3") (pin "2") (pinfunction "2_2") (pintype "passive"))
      (node (ref "R4") (pin "2") (pinfunction "2_2") (pintype "passive"))
      (node (ref "U1") (pin "31") (pinfunction "IO14_31") (pintype "bidirectional"))
    )
    (net (code "64") (name "/PA0") (class "Default")
      (node (ref "J1") (pin "1") (pinfunction "J_1") (pintype "passive"))
      (node (ref "U1") (pin "94") (pinfunction "IO51_94") (pintype "bidirectional"))
    )
    (net (code "65") (name "/PA1") (class "Default")
      (node (ref "J1") (pin "2") (pinfunction "J_2") (pintype "passive"))
      (node (ref "U1") (pin "96") (pinfunction "IO52_96") (pintype "bidirectional"))
    )
    (net (code "66") (name "/PA2") (class "Default")
      (node (ref "J1") (pin "3") (pinfunction "J_3") (pintype "passive"))
      (node (ref "U1") (pin "97") (pinfunction "IO53_97") (pintype "bidirectional"))
    )
    (net (code "67") (name "/PA3") (class "Default")
      (node (ref "J1") (pin "4") (pinfunction "J_4") (pintype "passive"))
      (node (ref "U1") (pin "99") (pinfunction "IO54_99") (pintype "bidirectional"))
    )
    (net (code "68") (name "/PA4") (class "Default")
      (node (ref "J1") (pin "5") (pinfunction "J_5") (pintype "passive"))
      (node (ref "U1") (pin "100") (pinfunction "IO55_100") (pintype "bidirectional"))
    )
    (net (code "69") (name "/PA5") (class "Default")
      (node (ref "J1") (pin "6") (pinfunction "J_6") (pintype "passive"))
      (node (ref "U1") (pin "101") (pinfunction "IO56_101") (pintype "bidirectional"))
    )
    (net (code "70") (name "/PA6") (class "Default")
      (node (ref "J1") (pin "7") (pinfunction "J_7") (pintype "passive"))
      (node (ref "U1") (pin "103") (pinfunction "IO57_103") (pintype "bidirectional"))
    )
    (net (code "71") (name "/PA7") (class "Default")
      (node (ref "J1") (pin "8") (pinfunction "J_8") (pintype "passive"))
      (node (ref "U1") (pin "104") (pinfunction "IO58_104") (pintype "bidirectional"))
    )
    (net (code "72") (name "/PA8") (class "Default")
      (node (ref "CON1") (pin "30") (pinfunction "PA8_30") (pintype "input"))
      (node (ref "U1") (pin "132") (pinfunction "IO71_132") (pintype "bidirectional"))
    )
    (net (code "73") (name "/PA9") (class "Default")
      (node (ref "CON1") (pin "29") (pinfunction "PA9_29") (pintype "input"))
      (node (ref "U1") (pin "129") (pinfunction "IO70_129") (pintype "bidirectional"))
    )
    (net (code "74") (name "/PA10") (class "Default")
      (node (ref "CON1") (pin "28") (pinfunction "PA10_28") (pintype "input"))
      (node (ref "U1") (pin "126") (pinfunction "IO69_126") (pintype "bidirectional"))
    )
    (net (code "75") (name "/PA11") (class "Default")
      (node (ref "CON1") (pin "27") (pinfunction "PA11_27") (pintype "input"))
      (node (ref "U1") (pin "125") (pinfunction "IO68_125") (pintype "bidirectional"))
    )
    (net (code "76") (name "/PA12") (class "Default")
      (node (ref "CON1") (pin "26") (pinfunction "PA12_26") (pintype "input"))
      (node (ref "U1") (pin "122") (pinfunction "IO67_122") (pintype "bidirectional"))
    )
    (net (code "77") (name "/PA13") (class "Default")
      (node (ref "CON1") (pin "25") (pinfunction "PA13_25") (pintype "input"))
      (node (ref "U1") (pin "121") (pinfunction "IO66_121") (pintype "bidirectional"))
    )
    (net (code "78") (name "/PALSEL0") (class "Default")
      (node (ref "JP7") (pin "2") (pinfunction "2_2") (pintype "passive"))
      (node (ref "R5") (pin "2") (pinfunction "2_2") (pintype "passive"))
      (node (ref "U1") (pin "28") (pinfunction "IO12_28") (pintype "bidirectional"))
    )
    (net (code "79") (name "/PALSEL1") (class "Default")
      (node (ref "JP8") (pin "2") (pinfunction "2_2") (pintype "passive"))
      (node (ref "R6") (pin "2") (pinfunction "2_2") (pintype "passive"))
      (node (ref "U1") (pin "30") (pinfunction "IO13_30") (pintype "bidirectional"))
    )
    (net (code "80") (name "/PD0") (class "Default")
      (node (ref "CON1") (pin "38") (pinfunction "PD0_38") (pintype "bidirectional"))
      (node (ref "U2") (pin "21") (pinfunction "B0_21") (pintype "bidirectional"))
    )
    (net (code "81") (name "/PD0_FPGA") (class "Default")
      (node (ref "U1") (pin "144") (pinfunction "IO81_144") (pintype "bidirectional"))
      (node (ref "U2") (pin "3") (pinfunction "A0_3") (pintype "bidirectional"))
    )
    (net (code "82") (name "/PD1") (class "Default")
      (node (ref "CON1") (pin "37") (pinfunction "PD1_37") (pintype "bidirectional"))
      (node (ref "U2") (pin "20") (pinfunction "B1_20") (pintype "bidirectional"))
    )
    (net (code "83") (name "/PD1_FPGA") (class "Default")
      (node (ref "U1") (pin "143") (pinfunction "IO80_143") (pintype "bidirectional"))
      (node (ref "U2") (pin "4") (pinfunction "A1_4") (pintype "bidirectional"))
    )
    (net (code "84") (name "/PD2") (class "Default")
      (node (ref "CON1") (pin "36") (pinfunction "PD2_36") (pintype "bidirectional"))
      (node (ref "U2") (pin "19") (pinfunction "B2_19") (pintype "bidirectional"))
    )
    (net (code "85") (name "/PD2_FPGA") (class "Default")
      (node (ref "U1") (pin "142") (pinfunction "IO79_142") (pintype "bidirectional"))
      (node (ref "U2") (pin "5") (pinfunction "A2_5") (pintype "bidirectional"))
    )
    (net (code "86") (name "/PD3") (class "Default")
      (node (ref "CON1") (pin "35") (pinfunction "PD3_35") (pintype "bidirectional"))
      (node (ref "U2") (pin "18") (pinfunction "B3_18") (pintype "bidirectional"))
    )
    (net (code "87") (name "/PD3_FPGA") (class "Default")
      (node (ref "U1") (pin "141") (pinfunction "IO78_141") (pintype "bidirectional"))
      (node (ref "U2") (pin "6") (pinfunction "A3_6") (pintype "bidirectional"))
    )
    (net (code "88") (name "/PD4") (class "Default")
      (node (ref "CON1") (pin "34") (pinfunction "PD4_34") (pintype "bidirectional"))
      (node (ref "U2") (pin "17") (pinfunction "B4_17") (pintype "bidirectional"))
    )
    (net (code "89") (name "/PD4_FPGA") (class "Default")
      (node (ref "U1") (pin "139") (pinfunction "IO77_139") (pintype "bidirectional"))
      (node (ref "U2") (pin "7") (pinfunction "A4_7") (pintype "bidirectional"))
    )
    (net (code "90") (name "/PD5") (class "Default")
      (node (ref "CON1") (pin "33") (pinfunction "PD5_33") (pintype "bidirectional"))
      (node (ref "U2") (pin "16") (pinfunction "B5_16") (pintype "bidirectional"))
    )
    (net (code "91") (name "/PD5_FPGA") (class "Default")
      (node (ref "U1") (pin "137") (pinfunction "IO76_137") (pintype "bidirectional"))
      (node (ref "U2") (pin "8") (pinfunction "A5_8") (pintype "bidirectional"))
    )
    (net (code "92") (name "/PD6") (class "Default")
      (node (ref "CON1") (pin "32") (pinfunction "PD6_32") (pintype "bidirectional"))
      (node (ref "U2") (pin "15") (pinfunction "B6_15") (pintype "bidirectional"))
    )
    (net (code "93") (name "/PD6_FPGA") (class "Default")
      (node (ref "U1") (pin "136") (pinfunction "IO75_136") (pintype "bidirectional"))
      (node (ref "U2") (pin "9") (pinfunction "A6_9") (pintype "bidirectional"))
    )
    (net (code "94") (name "/PD7") (class "Default")
      (node (ref "CON1") (pin "31") (pinfunction "PD7_31") (pintype "bidirectional"))
      (node (ref "U2") (pin "14") (pinfunction "B7_14") (pintype "bidirectional"))
    )
    (net (code "95") (name "/PD7_FPGA") (class "Default")
      (node (ref "U1") (pin "135") (pinfunction "IO74_135") (pintype "bidirectional"))
      (node (ref "U2") (pin "10") (pinfunction "A7_10") (pintype "bidirectional"))
    )
    (net (code "96") (name "/PD_OE") (class "Default")
      (node (ref "U1") (pin "133") (pinfunction "IO72_133") (pintype "bidirectional"))
      (node (ref "U2") (pin "22") (pinfunction "/OE_22") (pintype "input"))
    )
    (net (code "97") (name "/R0") (class "Default")
      (node (ref "U1") (pin "72") (pinfunction "IO39_72") (pintype "bidirectional"))
      (node (ref "U7") (pin "41") (pinfunction "R0_41") (pintype "input"))
    )
    (net (code "98") (name "/R1") (class "Default")
      (node (ref "U1") (pin "71") (pinfunction "IO38_71") (pintype "bidirectional"))
      (node (ref "U7") (pin "42") (pinfunction "R1_42") (pintype "input"))
    )
    (net (code "99") (name "/R2") (class "Default")
      (node (ref "U1") (pin "70") (pinfunction "IO37_70") (pintype "bidirectional"))
      (node (ref "U7") (pin "43") (pinfunction "R2_43") (pintype "input"))
    )
    (net (code "100") (name "/R3") (class "Default")
      (node (ref "U1") (pin "69") (pinfunction "IO36_69") (pintype "bidirectional"))
      (node (ref "U7") (pin "44") (pinfunction "R3_44") (pintype "input"))
    )
    (net (code "101") (name "/R4") (class "Default")
      (node (ref "U1") (pin "67") (pinfunction "IO35_67") (pintype "bidirectional"))
      (node (ref "U7") (pin "45") (pinfunction "R4_45") (pintype "input"))
    )
    (net (code "102") (name "/R5") (class "Default")
      (node (ref "U1") (pin "65") (pinfunction "IO34_65") (pintype "bidirectional"))
      (node (ref "U7") (pin "46") (pinfunction "R5_46") (pintype "input"))
    )
    (net (code "103") (name "/R6") (class "Default")
      (node (ref "U1") (pin "64") (pinfunction "IO33_64") (pintype "bidirectional"))
      (node (ref "U7") (pin "47") (pinfunction "R6_47") (pintype "input"))
    )
    (net (code "104") (name "/R7") (class "Default")
      (node (ref "U1") (pin "63") (pinfunction "IO32_63") (pintype "bidirectional"))
      (node (ref "U7") (pin "48") (pinfunction "R7_48") (pintype "input"))
    )
    (net (code "105") (name "/RW") (class "Default")
      (node (ref "CON1") (pin "1") (pinfunction "RW_1") (pintype "output"))
      (node (ref "U4") (pin "2") (pinfunction "A1_2") (pintype "input"))
    )
    (net (code "106") (name "/RW_FPGA") (class "Default")
      (node (ref "U1") (pin "119") (pinfunction "IO64_119") (pintype "bidirectional"))
      (node (ref "U3") (pin "2") (pinfunction "DIR_2") (pintype "input"))
      (node (ref "U4") (pin "18") (pinfunction "Y1_18") (pintype "output"))
    )
    (net (code "107") (name "/SYNC_FPGA") (class "Default")
      (node (ref "R23") (pin "1") (pinfunction "1_1") (pintype "passive"))
      (node (ref "U1") (pin "74") (pinfunction "IO41_74") (pintype "bidirectional"))
    )
    (net (code "108") (name "/TCK") (class "Default")
      (node (ref "R16") (pin "1") (pinfunction "1_1") (pintype "passive"))
      (node (ref "U1") (pin "12") (pinfunction "TCK_12") (pintype "input"))
      (node (ref "X1") (pin "1") (pinfunction "S_1") (pintype "passive"))
    )
    (net (code "109") (name "/TDI") (class "Default")
      (node (ref "R10") (pin "1") (pinfunction "1_1") (pintype "passive"))
      (node (ref "U1") (pin "13") (pinfunction "TDI_13") (pintype "input"))
      (node (ref "X1") (pin "9") (pinfunction "S_9") (pintype "passive"))
    )
    (net (code "110") (name "/TDO") (class "Default")
      (node (ref "U1") (pin "10") (pinfunction "TDO_10") (pintype "output"))
      (node (ref "X1") (pin "3") (pinfunction "S_3") (pintype "passive"))
    )
    (net (code "111") (name "/TMS") (class "Default")
      (node (ref "R11") (pin "1") (pinfunction "1_1") (pintype "passive"))
      (node (ref "U1") (pin "11") (pinfunction "TMS_11") (pintype "input"))
      (node (ref "X1") (pin "5") (pinfunction "S_5") (pintype "passive"))
    )
    (net (code "112") (name "/VPLL1") (class "Default")
      (node (ref "C15") (pin "1") (pinfunction "1_1") (pintype "passive"))
      (node (ref "C16") (pin "1") (pinfunction "1_1") (pintype "passive"))
      (node (ref "L1") (pin "1") (pinfunction "1_1") (pintype "passive"))
    )
    (net (code "113") (name "/VPLL2") (class "Default")
      (node (ref "C17") (pin "1") (pinfunction "1_1") (pintype "passive"))
      (node (ref "C18") (pin "1") (pinfunction "1_1") (pintype "passive"))
      (node (ref "L2") (pin "2") (pinfunction "2_2") (pintype "passive"))
    )
    (net (code "114") (name "/VPPL1") (class "Default")
      (node (ref "U1") (pin "35") (pinfunction "VPLL1_35") (pintype "power_in"))
      (node (ref "U1") (pin "37") (pinfunction "VAPLL1_37") (pintype "power_in"))
    )
    (net (code "115") (name "/VPPL2") (class "Default")
      (node (ref "U1") (pin "107") (pinfunction "VPLL2_107") (pintype "power_in"))
      (node (ref "U1") (pin "109") (pinfunction "VAPLL2_109") (pintype "power_in"))
    )
    (net (code "116") (name "/VRAMCS") (class "Default")
      (node (ref "JP6") (pin "1") (pinfunction "1_1") (pintype "passive"))
      (node (ref "U4") (pin "3") (pinfunction "A2_3") (pintype "input"))
    )
    (net (code "117") (name "/VRAM_A10") (class "Default")
      (node (ref "R1") (pin "2") (pinfunction "2_2") (pintype "passive"))
      (node (ref "U1") (pin "92") (pinfunction "IO49_92") (pintype "bidirectional"))
    )
    (net (code "118") (name "/VRCS_FPGA") (class "Default")
      (node (ref "U1") (pin "134") (pinfunction "IO73_134") (pintype "bidirectional"))
      (node (ref "U4") (pin "17") (pinfunction "Y2_17") (pintype "output"))
    )
    (net (code "119") (name "/VSYNC") (class "Default")
      (node (ref "R8") (pin "2") (pinfunction "2_2") (pintype "passive"))
      (node (ref "X2") (pin "6") (pinfunction "1_6") (pintype "passive"))
    )
    (net (code "120") (name "/{slash}CSO") (class "Default")
      (node (ref "U1") (pin "2") (pinfunction "IO2(/CSO)_2") (pintype "bidirectional"))
      (node (ref "U6") (pin "1") (pinfunction "/CS_1") (pintype "input"))
    )
    (net (code "121") (name "/{slash}DBE") (class "Default")
      (node (ref "CON1") (pin "13") (pinfunction "/DBE_13") (pintype "output"))
      (node (ref "U4") (pin "7") (pinfunction "A6_7") (pintype "input"))
    )
    (net (code "122") (name "/{slash}DBE_FPGA") (class "Default")
      (node (ref "U1") (pin "113") (pinfunction "IO60_113") (pintype "bidirectional"))
      (node (ref "U3") (pin "22") (pinfunction "/OE_22") (pintype "input"))
      (node (ref "U4") (pin "13") (pinfunction "Y6_13") (pintype "output"))
    )
    (net (code "123") (name "/{slash}INT") (class "Default")
      (node (ref "CON1") (pin "19") (pinfunction "/INT_19") (pintype "input"))
      (node (ref "T1") (pin "3") (pinfunction "C_3") (pintype "passive"))
    )
    (net (code "124") (name "/{slash}PRD") (class "Default")
      (node (ref "CON1") (pin "24") (pinfunction "/PRD_24") (pintype "input"))
      (node (ref "U1") (pin "120") (pinfunction "IO65_120") (pintype "bidirectional"))
      (node (ref "U2") (pin "2") (pinfunction "DIR_2") (pintype "input"))
    )
    (net (code "125") (name "/{slash}PWR") (class "Default")
      (node (ref "CON1") (pin "23") (pinfunction "/PWR_23") (pintype "input"))
      (node (ref "U1") (pin "112") (pinfunction "IO59_112") (pintype "bidirectional"))
    )
    (net (code "126") (name "AVCC") (class "Default")
      (node (ref "C10") (pin "1") (pinfunction "1_1") (pintype "passive"))
      (node (ref "C11") (pin "1") (pinfunction "1_1") (pintype "passive"))
      (node (ref "C40") (pin "1") (pinfunction "1_1") (pintype "passive"))
      (node (ref "C41") (pin "2") (pinfunction "2_2") (pintype "passive"))
      (node (ref "C42") (pin "2") (pinfunction "2_2") (pintype "passive"))
      (node (ref "C43") (pin "1") (pinfunction "1_1") (pintype "passive"))
      (node (ref "R25") (pin "2") (pinfunction "2_2") (pintype "passive"))
      (node (ref "U7") (pin "11") (pinfunction "/BLANK_11") (pintype "input"))
      (node (ref "U7") (pin "13") (pinfunction "VAA_13") (pintype "power_in"))
      (node (ref "U7") (pin "29") (pinfunction "VAA_29") (pintype "power_in"))
      (node (ref "U7") (pin "30") (pinfunction "VAA_30") (pintype "power_in"))
      (node (ref "U7") (pin "38") (pinfunction "/PSAVE_38") (pintype "input"))
      (node (ref "U8") (pin "10") (pinfunction "VS+_10") (pintype "power_in"))
      (node (ref "VR2") (pin "2") (pinfunction "VOUT_2") (pintype "power_in"))
    )
    (net (code "127") (name "GND") (class "Default")
      (node (ref "C1") (pin "1") (pinfunction "1_1") (pintype "passive"))
      (node (ref "C10") (pin "2") (pinfunction "2_2") (pintype "passive"))
      (node (ref "C11") (pin "2") (pinfunction "2_2") (pintype "passive"))
      (node (ref "C12") (pin "2") (pinfunction "2_2") (pintype "passive"))
      (node (ref "C13") (pin "2") (pinfunction "2_2") (pintype "passive"))
      (node (ref "C14") (pin "-") (pinfunction "-_-") (pintype "passive"))
      (node (ref "C15") (pin "2") (pinfunction "2_2") (pintype "passive"))
      (node (ref "C16") (pin "2") (pinfunction "2_2") (pintype "passive"))
      (node (ref "C17") (pin "2") (pinfunction "2_2") (pintype "passive"))
      (node (ref "C18") (pin "2") (pinfunction "2_2") (pintype "passive"))
      (node (ref "C19") (pin "2") (pinfunction "2_2") (pintype "passive"))
      (node (ref "C2") (pin "1") (pinfunction "1_1") (pintype "passive"))
      (node (ref "C20") (pin "1") (pinfunction "1_1") (pintype "passive"))
      (node (ref "C21") (pin "1") (pinfunction "1_1") (pintype "passive"))
      (node (ref "C22") (pin "1") (pinfunction "1_1") (pintype "passive"))
      (node (ref "C23") (pin "1") (pinfunction "1_1") (pintype "passive"))
      (node (ref "C24") (pin "1") (pinfunction "1_1") (pintype "passive"))
      (node (ref "C25") (pin "1") (pinfunction "1_1") (pintype "passive"))
      (node (ref "C26") (pin "1") (pinfunction "1_1") (pintype "passive"))
      (node (ref "C27") (pin "1") (pinfunction "1_1") (pintype "passive"))
      (node (ref "C28") (pin "1") (pinfunction "1_1") (pintype "passive"))
      (node (ref "C29") (pin "2") (pinfunction "2_2") (pintype "passive"))
      (node (ref "C3") (pin "1") (pinfunction "1_1") (pintype "passive"))
      (node (ref "C30") (pin "2") (pinfunction "2_2") (pintype "passive"))
      (node (ref "C31") (pin "2") (pinfunction "2_2") (pintype "passive"))
      (node (ref "C32") (pin "2") (pinfunction "2_2") (pintype "passive"))
      (node (ref "C33") (pin "2") (pinfunction "2_2") (pintype "passive"))
      (node (ref "C34") (pin "2") (pinfunction "2_2") (pintype "passive"))
      (node (ref "C35") (pin "2") (pinfunction "2_2") (pintype "passive"))
      (node (ref "C36") (pin "2") (pinfunction "2_2") (pintype "passive"))
      (node (ref "C37") (pin "2") (pinfunction "2_2") (pintype "passive"))
      (node (ref "C38") (pin "2") (pinfunction "2_2") (pintype "passive"))
      (node (ref "C4") (pin "1") (pinfunction "1_1") (pintype "passive"))
      (node (ref "C40") (pin "2") (pinfunction "2_2") (pintype "passive"))
      (node (ref "C43") (pin "2") (pinfunction "2_2") (pintype "passive"))
      (node (ref "C5") (pin "-") (pinfunction "-_-") (pintype "passive"))
      (node (ref "C6") (pin "2") (pinfunction "2_2") (pintype "passive"))
      (node (ref "C7") (pin "2") (pinfunction "2_2") (pintype "passive"))
      (node (ref "C8") (pin "-") (pinfunction "-_-") (pintype "passive"))
      (node (ref "C9") (pin "2") (pinfunction "2_2") (pintype "passive"))
      (node (ref "CON1") (pin "20") (pinfunction "GND_20") (pintype "power_in"))
      (node (ref "JP1") (pin "2") (pinfunction "2_2") (pintype "passive"))
      (node (ref "JP2") (pin "1") (pinfunction "1_1") (pintype "passive"))
      (node (ref "JP2") (pin "11") (pinfunction "1_11") (pintype "passive"))
      (node (ref "JP2") (pin "3") (pinfunction "1_3") (pintype "passive"))
      (node (ref "JP2") (pin "5") (pinfunction "1_5") (pintype "passive"))
      (node (ref "JP2") (pin "7") (pinfunction "1_7") (pintype "passive"))
      (node (ref "JP2") (pin "9") (pinfunction "1_9") (pintype "passive"))
      (node (ref "JP3") (pin "1") (pinfunction "1_1") (pintype "passive"))
      (node (ref "JP4") (pin "1") (pinfunction "1_1") (pintype "passive"))
      (node (ref "JP7") (pin "1") (pinfunction "1_1") (pintype "passive"))
      (node (ref "JP8") (pin "1") (pinfunction "1_1") (pintype "passive"))
      (node (ref "Q1") (pin "2") (pinfunction "GND_2") (pintype "power_in"))
      (node (ref "Q2") (pin "2") (pinfunction "GND_2") (pintype "power_in"))
      (node (ref "Q3") (pin "2") (pinfunction "GND_2") (pintype "power_in"))
      (node (ref "R15") (pin "2") (pinfunction "2_2") (pintype "passive"))
      (node (ref "R16") (pin "2") (pinfunction "2_2") (pintype "passive"))
      (node (ref "R17") (pin "2") (pinfunction "2_2") (pintype "passive"))
      (node (ref "R19") (pin "1") (pinfunction "1_1") (pintype "passive"))
      (node (ref "R20") (pin "1") (pinfunction "1_1") (pintype "passive"))
      (node (ref "R21") (pin "1") (pinfunction "1_1") (pintype "passive"))
      (node (ref "R22") (pin "1") (pinfunction "1_1") (pintype "passive"))
      (node (ref "R24") (pin "2") (pinfunction "2_2") (pintype "passive"))
      (node (ref "R3") (pin "2") (pinfunction "2_2") (pintype "passive"))
      (node (ref "T1") (pin "2") (pinfunction "E_2") (pintype "passive"))
      (node (ref "U1") (pin "105") (pinfunction "GND_105") (pintype "power_in"))
      (node (ref "U1") (pin "106") (pinfunction "GPLL2_106") (pintype "power_in"))
      (node (ref "U1") (pin "108") (pinfunction "GPLL2_108") (pintype "power_in"))
      (node (ref "U1") (pin "110") (pinfunction "GAPLL2_110") (pintype "power_in"))
      (node (ref "U1") (pin "111") (pinfunction "GND_111") (pintype "power_in"))
      (node (ref "U1") (pin "117") (pinfunction "GND_117") (pintype "power_in"))
      (node (ref "U1") (pin "123") (pinfunction "GND_123") (pintype "power_in"))
      (node (ref "U1") (pin "128") (pinfunction "GND_128") (pintype "power_in"))
      (node (ref "U1") (pin "130") (pinfunction "GND_130") (pintype "power_in"))
      (node (ref "U1") (pin "140") (pinfunction "GND_140") (pintype "power_in"))
      (node (ref "U1") (pin "19") (pinfunction "GND_19") (pintype "power_in"))
      (node (ref "U1") (pin "33") (pinfunction "GND_33") (pintype "power_in"))
      (node (ref "U1") (pin "34") (pinfunction "GPLL1_34") (pintype "power_in"))
      (node (ref "U1") (pin "36") (pinfunction "GPLL1_36") (pintype "power_in"))
      (node (ref "U1") (pin "38") (pinfunction "GAPLL1_38") (pintype "power_in"))
      (node (ref "U1") (pin "39") (pinfunction "GND_39") (pintype "power_in"))
      (node (ref "U1") (pin "49") (pinfunction "GND_49") (pintype "power_in"))
      (node (ref "U1") (pin "56") (pinfunction "GND_56") (pintype "power_in"))
      (node (ref "U1") (pin "6") (pinfunction "GND_6") (pintype "power_in"))
      (node (ref "U1") (pin "61") (pinfunction "GND_61") (pintype "power_in"))
      (node (ref "U1") (pin "68") (pinfunction "GND_68") (pintype "power_in"))
      (node (ref "U1") (pin "78") (pinfunction "GND_78") (pintype "power_in"))
      (node (ref "U1") (pin "84") (pinfunction "MSEL1_84") (pintype "input"))
      (node (ref "U1") (pin "85") (pinfunction "MSEL0_85") (pintype "input"))
      (node (ref "U1") (pin "98") (pinfunction "GND_98") (pintype "power_in"))
      (node (ref "U2") (pin "11") (pinfunction "GND_11") (pintype "power_in"))
      (node (ref "U2") (pin "12") (pinfunction "GND_12") (pintype "power_in"))
      (node (ref "U2") (pin "13") (pinfunction "GND_13") (pintype "power_in"))
      (node (ref "U3") (pin "11") (pinfunction "GND_11") (pintype "power_in"))
      (node (ref "U3") (pin "12") (pinfunction "GND_12") (pintype "power_in"))
      (node (ref "U3") (pin "13") (pinfunction "GND_13") (pintype "power_in"))
      (node (ref "U4") (pin "1") (pinfunction "/OE1_1") (pintype "input"))
      (node (ref "U4") (pin "10") (pinfunction "GND_10") (pintype "power_in"))
      (node (ref "U4") (pin "19") (pinfunction "/OE2_19") (pintype "input"))
      (node (ref "U4") (pin "8") (pinfunction "A7_8") (pintype "input"))
      (node (ref "U4") (pin "9") (pinfunction "A8_9") (pintype "input"))
      (node (ref "U5") (pin "3") (pinfunction "GND_3") (pintype "power_in"))
      (node (ref "U6") (pin "4") (pinfunction "GND_4") (pintype "power_in"))
      (node (ref "U7") (pin "1") (pinfunction "GND_1") (pintype "power_in"))
      (node (ref "U7") (pin "12") (pinfunction "/SYNC_12") (pintype "input"))
      (node (ref "U7") (pin "14") (pinfunction "GND_14") (pintype "power_in"))
      (node (ref "U7") (pin "15") (pinfunction "GND_15") (pintype "power_in"))
      (node (ref "U7") (pin "2") (pinfunction "GND_2") (pintype "power_in"))
      (node (ref "U7") (pin "25") (pinfunction "GND_25") (pintype "power_in"))
      (node (ref "U7") (pin "26") (pinfunction "GND_26") (pintype "power_in"))
      (node (ref "U7") (pin "27") (pinfunction "/IOB_27") (pintype "bidirectional"))
      (node (ref "U7") (pin "31") (pinfunction "/IOG_31") (pintype "bidirectional"))
      (node (ref "U7") (pin "33") (pinfunction "/IOR_33") (pintype "bidirectional"))
      (node (ref "U7") (pin "39") (pinfunction "GND_39") (pintype "power_in"))
      (node (ref "U7") (pin "40") (pinfunction "GND_40") (pintype "power_in"))
      (node (ref "U8") (pin "5") (pinfunction "GND_5") (pintype "power_in"))
      (node (ref "U8") (pin "6") (pinfunction "DISABLE_6") (pintype "input"))
      (node (ref "VR1") (pin "1") (pinfunction "GND_1") (pintype "power_in"))
      (node (ref "VR2") (pin "1") (pinfunction "GND_1") (pintype "power_in"))
      (node (ref "VR3") (pin "1") (pinfunction "GND_1") (pintype "bidirectional"))
      (node (ref "X1") (pin "10") (pinfunction "S_10") (pintype "passive"))
      (node (ref "X1") (pin "2") (pinfunction "S_2") (pintype "passive"))
      (node (ref "X2") (pin "1") (pinfunction "1_1") (pintype "passive"))
    )
    (net (code "128") (name "Net-(C44-Pad+)") (class "Default")
      (node (ref "C44") (pin "+") (pinfunction "+_+") (pintype "passive"))
      (node (ref "R26") (pin "1") (pinfunction "1_1") (pintype "passive"))
    )
    (net (code "129") (name "Net-(C45-Pad+)") (class "Default")
      (node (ref "C45") (pin "+") (pinfunction "+_+") (pintype "passive"))
      (node (ref "R27") (pin "1") (pinfunction "1_1") (pintype "passive"))
    )
    (net (code "130") (name "Net-(C46-Pad+)") (class "Default")
      (node (ref "C46") (pin "+") (pinfunction "+_+") (pintype "passive"))
      (node (ref "R28") (pin "1") (pinfunction "1_1") (pintype "passive"))
    )
    (net (code "131") (name "Net-(C47-Pad+)") (class "Default")
      (node (ref "C47") (pin "+") (pinfunction "+_+") (pintype "passive"))
      (node (ref "R29") (pin "1") (pinfunction "1_1") (pintype "passive"))
    )
    (net (code "132") (name "Net-(JP5-Pad1)") (class "Default")
      (node (ref "JP5") (pin "1") (pinfunction "1_1") (pintype "passive"))
      (node (ref "R1") (pin "1") (pinfunction "1_1") (pintype "passive"))
    )
    (net (code "133") (name "Net-(LED1-C)") (class "Default")
      (node (ref "LED1") (pin "C@1") (pinfunction "C_C@1") (pintype "passive"))
      (node (ref "R3") (pin "1") (pinfunction "1_1") (pintype "passive"))
    )
    (net (code "134") (name "Net-(Q1-VDD)") (class "Default")
      (node (ref "C36") (pin "1") (pinfunction "1_1") (pintype "passive"))
      (node (ref "C38") (pin "1") (pinfunction "1_1") (pintype "passive"))
      (node (ref "L3") (pin "2") (pinfunction "2_2") (pintype "passive"))
      (node (ref "Q1") (pin "4") (pinfunction "VDD_4") (pintype "power_in"))
      (node (ref "Q2") (pin "4") (pinfunction "VDD_4") (pintype "power_in"))
    )
    (net (code "135") (name "Net-(Q3-VDD)") (class "Default")
      (node (ref "C37") (pin "1") (pinfunction "1_1") (pintype "passive"))
      (node (ref "L4") (pin "2") (pinfunction "2_2") (pintype "passive"))
      (node (ref "Q3") (pin "4") (pinfunction "VDD_4") (pintype "power_in"))
    )
    (net (code "136") (name "Net-(T1-B)") (class "Default")
      (node (ref "R2") (pin "1") (pinfunction "1_1") (pintype "passive"))
      (node (ref "T1") (pin "1") (pinfunction "B_1") (pintype "passive"))
    )
    (net (code "137") (name "Net-(U1-IO40)") (class "Default")
      (node (ref "R8") (pin "1") (pinfunction "1_1") (pintype "passive"))
      (node (ref "U1") (pin "73") (pinfunction "IO40_73") (pintype "bidirectional"))
    )
    (net (code "138") (name "Net-(U1-IO42)") (class "Default")
      (node (ref "R9") (pin "1") (pinfunction "1_1") (pintype "passive"))
      (node (ref "U1") (pin "75") (pinfunction "IO42_75") (pintype "bidirectional"))
    )
    (net (code "139") (name "Net-(U5-A)") (class "Default")
      (node (ref "C39") (pin "2") (pinfunction "2_2") (pintype "passive"))
      (node (ref "R17") (pin "1") (pinfunction "1_1") (pintype "passive"))
      (node (ref "U5") (pin "2") (pinfunction "A_2") (pintype "input"))
    )
    (net (code "140") (name "Net-(U7-CLK)") (class "Default")
      (node (ref "R18") (pin "2") (pinfunction "2_2") (pintype "passive"))
      (node (ref "U7") (pin "24") (pinfunction "CLK_24") (pintype "input"))
    )
    (net (code "141") (name "Net-(U7-COMP)") (class "Default")
      (node (ref "C42") (pin "1") (pinfunction "1_1") (pintype "passive"))
      (node (ref "U7") (pin "35") (pinfunction "COMP_35") (pintype "bidirectional"))
    )
    (net (code "142") (name "Net-(U7-IOB)") (class "Default")
      (node (ref "R22") (pin "2") (pinfunction "2_2") (pintype "passive"))
      (node (ref "U7") (pin "28") (pinfunction "IOB_28") (pintype "output"))
      (node (ref "U8") (pin "3") (pinfunction "CH3_IN_3") (pintype "input"))
    )
    (net (code "143") (name "Net-(U7-IOG)") (class "Default")
      (node (ref "R21") (pin "2") (pinfunction "2_2") (pintype "passive"))
      (node (ref "U7") (pin "32") (pinfunction "IOG_32") (pintype "output"))
      (node (ref "U8") (pin "2") (pinfunction "CH2_IN_2") (pintype "input"))
    )
    (net (code "144") (name "Net-(U7-IOR)") (class "Default")
      (node (ref "R20") (pin "2") (pinfunction "2_2") (pintype "passive"))
      (node (ref "U7") (pin "34") (pinfunction "IOR_34") (pintype "output"))
      (node (ref "U8") (pin "1") (pinfunction "CH1_IN_1") (pintype "input"))
    )
    (net (code "145") (name "Net-(U7-RSET)") (class "Default")
      (node (ref "R19") (pin "2") (pinfunction "2_2") (pintype "passive"))
      (node (ref "U7") (pin "37") (pinfunction "RSET_37") (pintype "input"))
    )
    (net (code "146") (name "Net-(U7-VREF)") (class "Default")
      (node (ref "C41") (pin "1") (pinfunction "1_1") (pintype "passive"))
      (node (ref "U7") (pin "36") (pinfunction "VREF_36") (pintype "bidirectional"))
    )
    (net (code "147") (name "Net-(U8-BYPASS)") (class "Default")
      (node (ref "JP1") (pin "1") (pinfunction "1_1") (pintype "passive"))
      (node (ref "R25") (pin "1") (pinfunction "1_1") (pintype "passive"))
      (node (ref "U8") (pin "9") (pinfunction "BYPASS_9") (pintype "input"))
    )
    (net (code "148") (name "Net-(U8-CH1_OUT)") (class "Default")
      (node (ref "R26") (pin "2") (pinfunction "2_2") (pintype "passive"))
      (node (ref "U8") (pin "14") (pinfunction "CH1_OUT_14") (pintype "output"))
    )
    (net (code "149") (name "Net-(U8-CH2_OUT)") (class "Default")
      (node (ref "R27") (pin "2") (pinfunction "2_2") (pintype "passive"))
      (node (ref "U8") (pin "13") (pinfunction "CH2_OUT_13") (pintype "output"))
    )
    (net (code "150") (name "Net-(U8-CH3_OUT)") (class "Default")
      (node (ref "R28") (pin "2") (pinfunction "2_2") (pintype "passive"))
      (node (ref "U8") (pin "12") (pinfunction "CH3_OUT_12") (pintype "output"))
    )
    (net (code "151") (name "Net-(U8-CH4_IN)") (class "Default")
      (node (ref "R23") (pin "2") (pinfunction "2_2") (pintype "passive"))
      (node (ref "R24") (pin "1") (pinfunction "1_1") (pintype "passive"))
      (node (ref "U8") (pin "4") (pinfunction "CH4_IN_4") (pintype "input"))
    )
    (net (code "152") (name "Net-(U8-CH4_OUT)") (class "Default")
      (node (ref "R29") (pin "2") (pinfunction "2_2") (pintype "passive"))
      (node (ref "U8") (pin "11") (pinfunction "CH4_OUT_11") (pintype "output"))
    )
    (net (code "153") (name "Net-(X2B-1)") (class "Default")
      (node (ref "C44") (pin "-") (pinfunction "-_-") (pintype "passive"))
      (node (ref "X2") (pin "2") (pinfunction "1_2") (pintype "passive"))
    )
    (net (code "154") (name "Net-(X2C-1)") (class "Default")
      (node (ref "C45") (pin "-") (pinfunction "-_-") (pintype "passive"))
      (node (ref "X2") (pin "3") (pinfunction "1_3") (pintype "passive"))
    )
    (net (code "155") (name "Net-(X2D-1)") (class "Default")
      (node (ref "C46") (pin "-") (pinfunction "-_-") (pintype "passive"))
      (node (ref "X2") (pin "4") (pinfunction "1_4") (pintype "passive"))
    )
    (net (code "156") (name "Net-(X2E-1)") (class "Default")
      (node (ref "C47") (pin "-") (pinfunction "-_-") (pintype "passive"))
      (node (ref "X2") (pin "5") (pinfunction "1_5") (pintype "passive"))
    )
    (net (code "157") (name "VCCINT") (class "Default")
      (node (ref "C13") (pin "1") (pinfunction "1_1") (pintype "passive"))
      (node (ref "C14") (pin "+") (pinfunction "+_+") (pintype "passive"))
      (node (ref "C25") (pin "2") (pinfunction "2_2") (pintype "passive"))
      (node (ref "C27") (pin "2") (pinfunction "2_2") (pintype "passive"))
      (node (ref "C33") (pin "1") (pinfunction "1_1") (pintype "passive"))
      (node (ref "C34") (pin "1") (pinfunction "1_1") (pintype "passive"))
      (node (ref "L1") (pin "2") (pinfunction "2_2") (pintype "passive"))
      (node (ref "L2") (pin "1") (pinfunction "1_1") (pintype "passive"))
      (node (ref "U1") (pin "124") (pinfunction "VCCINT_124") (pintype "power_in"))
      (node (ref "U1") (pin "131") (pinfunction "VCCINT_131") (pintype "power_in"))
      (node (ref "U1") (pin "50") (pinfunction "VCCINT_50") (pintype "power_in"))
      (node (ref "U1") (pin "62") (pinfunction "VCCINT_62") (pintype "power_in"))
      (node (ref "VR3") (pin "2") (pinfunction "VOUT_2") (pintype "bidirectional"))
    )
    (net (code "158") (name "VCCIO") (class "Default")
      (node (ref "C1") (pin "2") (pinfunction "2_2") (pintype "passive"))
      (node (ref "C12") (pin "1") (pinfunction "1_1") (pintype "passive"))
      (node (ref "C19") (pin "1") (pinfunction "1_1") (pintype "passive"))
      (node (ref "C21") (pin "2") (pinfunction "2_2") (pintype "passive"))
      (node (ref "C22") (pin "2") (pinfunction "2_2") (pintype "passive"))
      (node (ref "C23") (pin "2") (pinfunction "2_2") (pintype "passive"))
      (node (ref "C24") (pin "2") (pinfunction "2_2") (pintype "passive"))
      (node (ref "C26") (pin "2") (pinfunction "2_2") (pintype "passive"))
      (node (ref "C28") (pin "2") (pinfunction "2_2") (pintype "passive"))
      (node (ref "C29") (pin "1") (pinfunction "1_1") (pintype "passive"))
      (node (ref "C3") (pin "2") (pinfunction "2_2") (pintype "passive"))
      (node (ref "C30") (pin "1") (pinfunction "1_1") (pintype "passive"))
      (node (ref "C31") (pin "1") (pinfunction "1_1") (pintype "passive"))
      (node (ref "C32") (pin "1") (pinfunction "1_1") (pintype "passive"))
      (node (ref "C35") (pin "1") (pinfunction "1_1") (pintype "passive"))
      (node (ref "C7") (pin "1") (pinfunction "1_1") (pintype "passive"))
      (node (ref "L3") (pin "1") (pinfunction "1_1") (pintype "passive"))
      (node (ref "L4") (pin "1") (pinfunction "1_1") (pintype "passive"))
      (node (ref "LED1") (pin "A@1") (pinfunction "A_A@1") (pintype "passive"))
      (node (ref "R10") (pin "2") (pinfunction "2_2") (pintype "passive"))
      (node (ref "R11") (pin "2") (pinfunction "2_2") (pintype "passive"))
      (node (ref "R12") (pin "1") (pinfunction "1_1") (pintype "passive"))
      (node (ref "R13") (pin "2") (pinfunction "2_2") (pintype "passive"))
      (node (ref "R14") (pin "2") (pinfunction "2_2") (pintype "passive"))
      (node (ref "R4") (pin "1") (pinfunction "1_1") (pintype "passive"))
      (node (ref "R5") (pin "1") (pinfunction "1_1") (pintype "passive"))
      (node (ref "R6") (pin "1") (pinfunction "1_1") (pintype "passive"))
      (node (ref "R7") (pin "1") (pinfunction "1_1") (pintype "passive"))
      (node (ref "U1") (pin "102") (pinfunction "VCCIO3_102") (pintype "power_in"))
      (node (ref "U1") (pin "116") (pinfunction "VCCIO2_116") (pintype "power_in"))
      (node (ref "U1") (pin "127") (pinfunction "VCCIO2_127") (pintype "power_in"))
      (node (ref "U1") (pin "138") (pinfunction "VCCIO2_138") (pintype "power_in"))
      (node (ref "U1") (pin "23") (pinfunction "VCCIO1_23") (pintype "power_in"))
      (node (ref "U1") (pin "29") (pinfunction "VCCIO1_29") (pintype "power_in"))
      (node (ref "U1") (pin "46") (pinfunction "VCCIO4_46") (pintype "power_in"))
      (node (ref "U1") (pin "5") (pinfunction "VCCIO1_5") (pintype "power_in"))
      (node (ref "U1") (pin "54") (pinfunction "VCCIO4_54") (pintype "power_in"))
      (node (ref "U1") (pin "66") (pinfunction "VCCIO4_66") (pintype "power_in"))
      (node (ref "U1") (pin "77") (pinfunction "VCCIO3_77") (pintype "power_in"))
      (node (ref "U1") (pin "95") (pinfunction "VCCIO3_95") (pintype "power_in"))
      (node (ref "U2") (pin "1") (pinfunction "VCCA_1") (pintype "power_in"))
      (node (ref "U3") (pin "1") (pinfunction "VCCA_1") (pintype "power_in"))
      (node (ref "U4") (pin "20") (pinfunction "VCC_20") (pintype "power_in"))
      (node (ref "U5") (pin "5") (pinfunction "VCC_5") (pintype "power_in"))
      (node (ref "U6") (pin "3") (pinfunction "VCC_3") (pintype "power_in"))
      (node (ref "U6") (pin "7") (pinfunction "VCC_7") (pintype "power_in"))
      (node (ref "U6") (pin "8") (pinfunction "VCC_8") (pintype "power_in"))
      (node (ref "VR1") (pin "2") (pinfunction "VOUT_2") (pintype "power_in"))
      (node (ref "VR3") (pin "3") (pinfunction "VIN_3") (pintype "bidirectional"))
      (node (ref "X1") (pin "4") (pinfunction "S_4") (pintype "passive"))
    )
    (net (code "159") (name "unconnected-(CON1-EXT0-Pad14)") (class "Default")
      (node (ref "CON1") (pin "14") (pinfunction "EXT0_14") (pintype "bidirectional"))
    )
    (net (code "160") (name "unconnected-(CON1-EXT1-Pad15)") (class "Default")
      (node (ref "CON1") (pin "15") (pinfunction "EXT1_15") (pintype "bidirectional"))
    )
    (net (code "161") (name "unconnected-(CON1-EXT2-Pad16)") (class "Default")
      (node (ref "CON1") (pin "16") (pinfunction "EXT2_16") (pintype "bidirectional"))
    )
    (net (code "162") (name "unconnected-(CON1-EXT3-Pad17)") (class "Default")
      (node (ref "CON1") (pin "17") (pinfunction "EXT3_17") (pintype "bidirectional"))
    )
    (net (code "163") (name "unconnected-(CON1-VOUT-Pad21)") (class "Default")
      (node (ref "CON1") (pin "21") (pinfunction "VOUT_21") (pintype "no_connect"))
    )
    (net (code "164") (name "unconnected-(CON1-{slash}RES-Pad22)") (class "Default")
      (node (ref "CON1") (pin "22") (pinfunction "/RES_22") (pintype "no_connect"))
    )
    (net (code "165") (name "unconnected-(Q1-TS-Pad1)") (class "Default")
      (node (ref "Q1") (pin "1") (pinfunction "TS_1") (pintype "passive"))
    )
    (net (code "166") (name "unconnected-(Q2-TS-Pad1)") (class "Default")
      (node (ref "Q2") (pin "1") (pinfunction "TS_1") (pintype "passive"))
    )
    (net (code "167") (name "unconnected-(Q3-TS-Pad1)") (class "Default")
      (node (ref "Q3") (pin "1") (pinfunction "TS_1") (pintype "passive"))
    )
    (net (code "168") (name "unconnected-(U1-CLK1-Pad18)") (class "Default")
      (node (ref "U1") (pin "18") (pinfunction "CLK1_18") (pintype "input"))
    )
    (net (code "169") (name "unconnected-(U1-CLK2-Pad21)") (class "Default")
      (node (ref "U1") (pin "21") (pinfunction "CLK2_21") (pintype "input"))
    )
    (net (code "170") (name "unconnected-(U1-CLK3-Pad22)") (class "Default")
      (node (ref "U1") (pin "22") (pinfunction "CLK3_22") (pintype "input"))
    )
    (net (code "171") (name "unconnected-(U1-CLK5-Pad90)") (class "Default")
      (node (ref "U1") (pin "90") (pinfunction "CLK5_90") (pintype "input"))
    )
    (net (code "172") (name "unconnected-(U4-Y7-Pad12)") (class "Default")
      (node (ref "U4") (pin "12") (pinfunction "Y7_12") (pintype "output"))
    )
    (net (code "173") (name "unconnected-(U4-Y8-Pad11)") (class "Default")
      (node (ref "U4") (pin "11") (pinfunction "Y8_11") (pintype "output"))
    )
    (net (code "174") (name "unconnected-(U5-N.C-Pad1)") (class "Default")
      (node (ref "U5") (pin "1") (pinfunction "N.C_1") (pintype "no_connect"))
    )
    (net (code "175") (name "unconnected-(X1G-S-Pad6)") (class "Default")
      (node (ref "X1") (pin "6") (pinfunction "S_6") (pintype "passive"))
    )
    (net (code "176") (name "unconnected-(X1H-S-Pad7)") (class "Default")
      (node (ref "X1") (pin "7") (pinfunction "S_7") (pintype "passive"))
    )
    (net (code "177") (name "unconnected-(X1I-S-Pad8)") (class "Default")
      (node (ref "X1") (pin "8") (pinfunction "S_8") (pintype "passive"))
    )
  )
)
